# PT_2015_PB_MAIN_Rev2.net
KiCad netlist of a schematic drawn in EAGLE
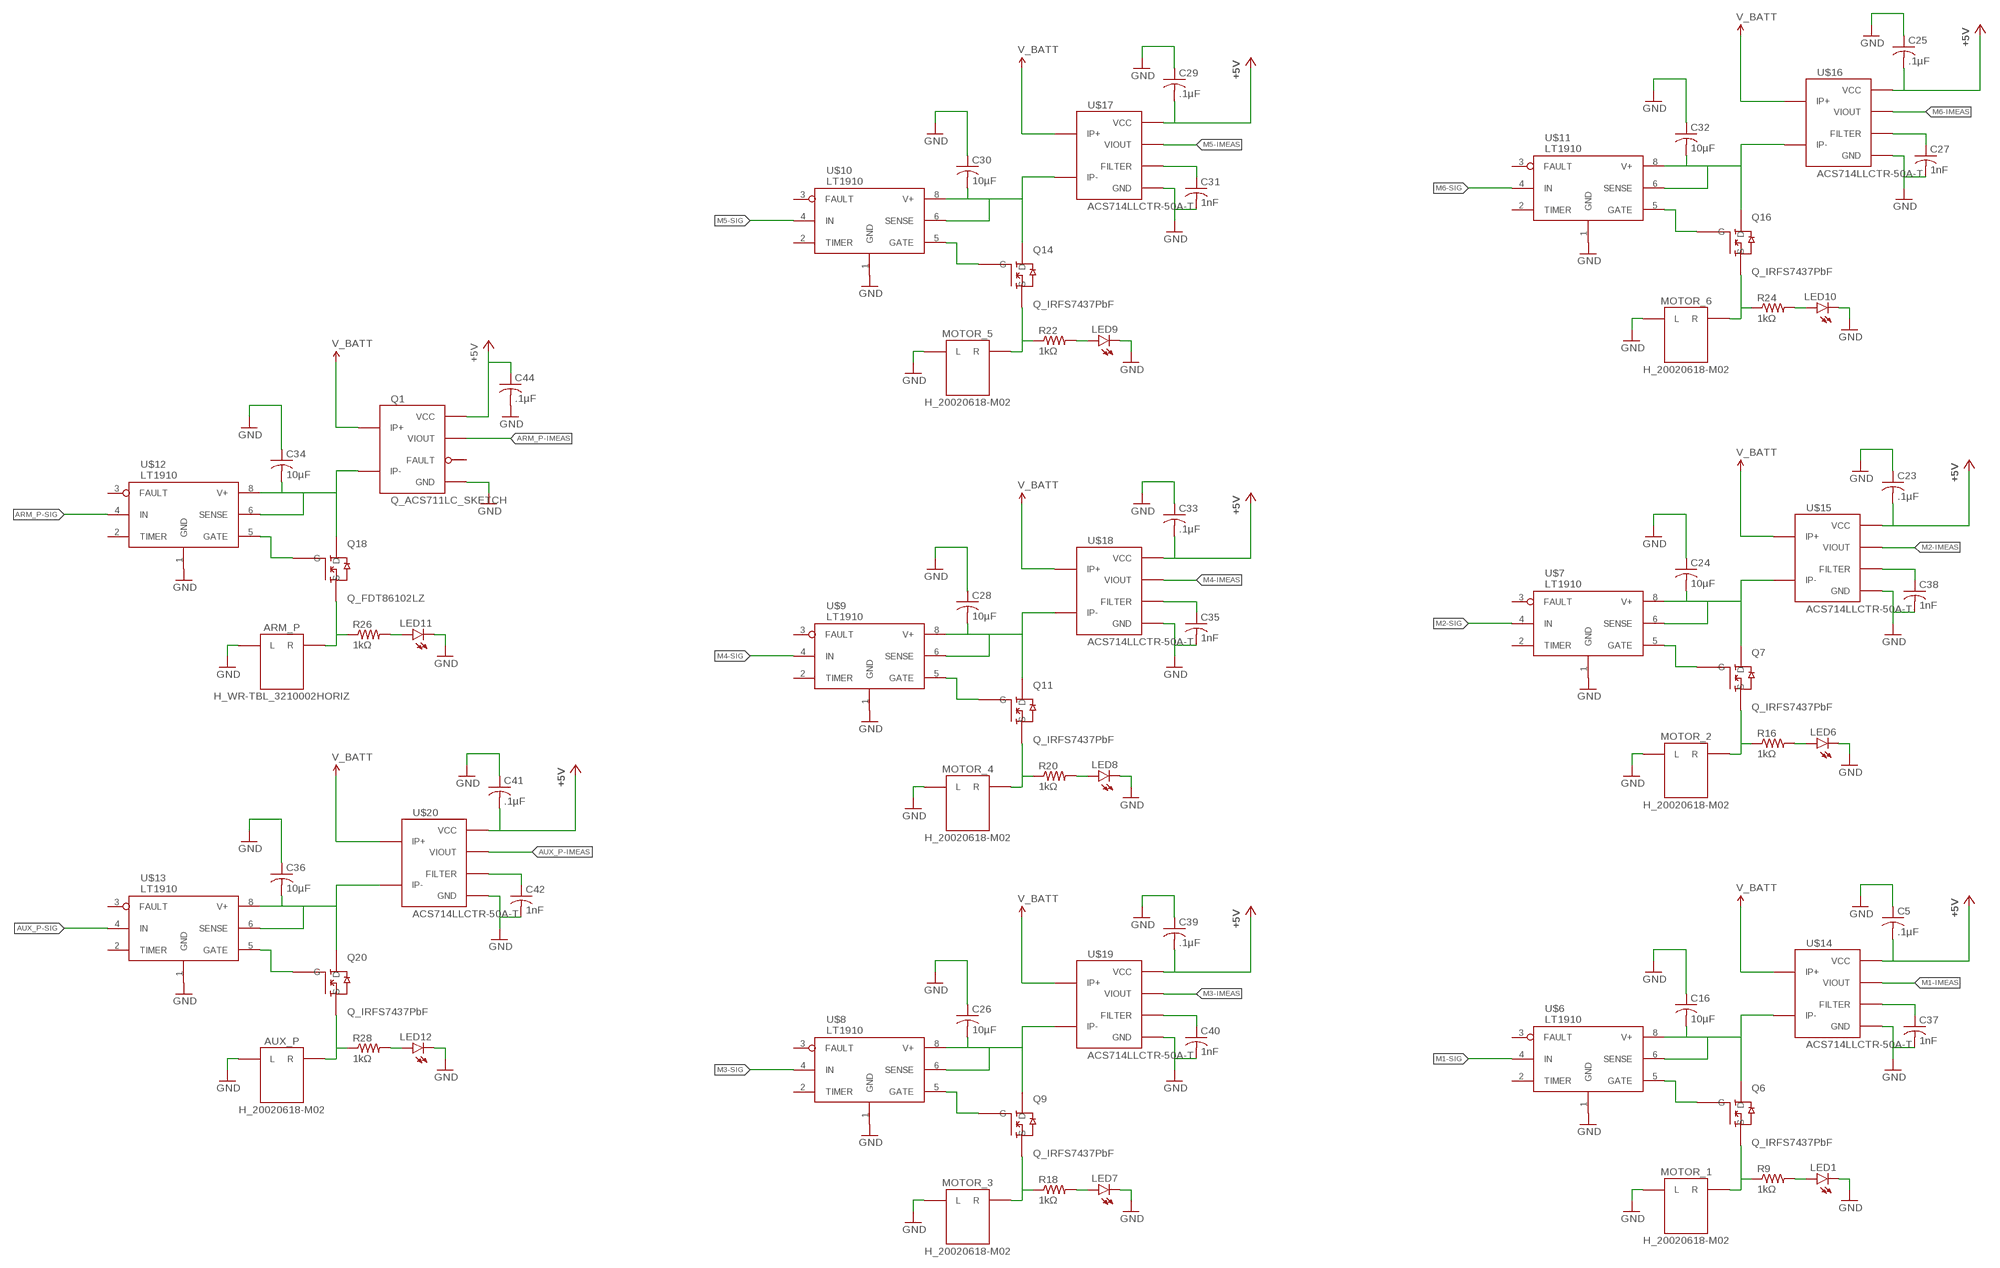
[diagram p0: schematic, sheet 1, part 1 of 3]
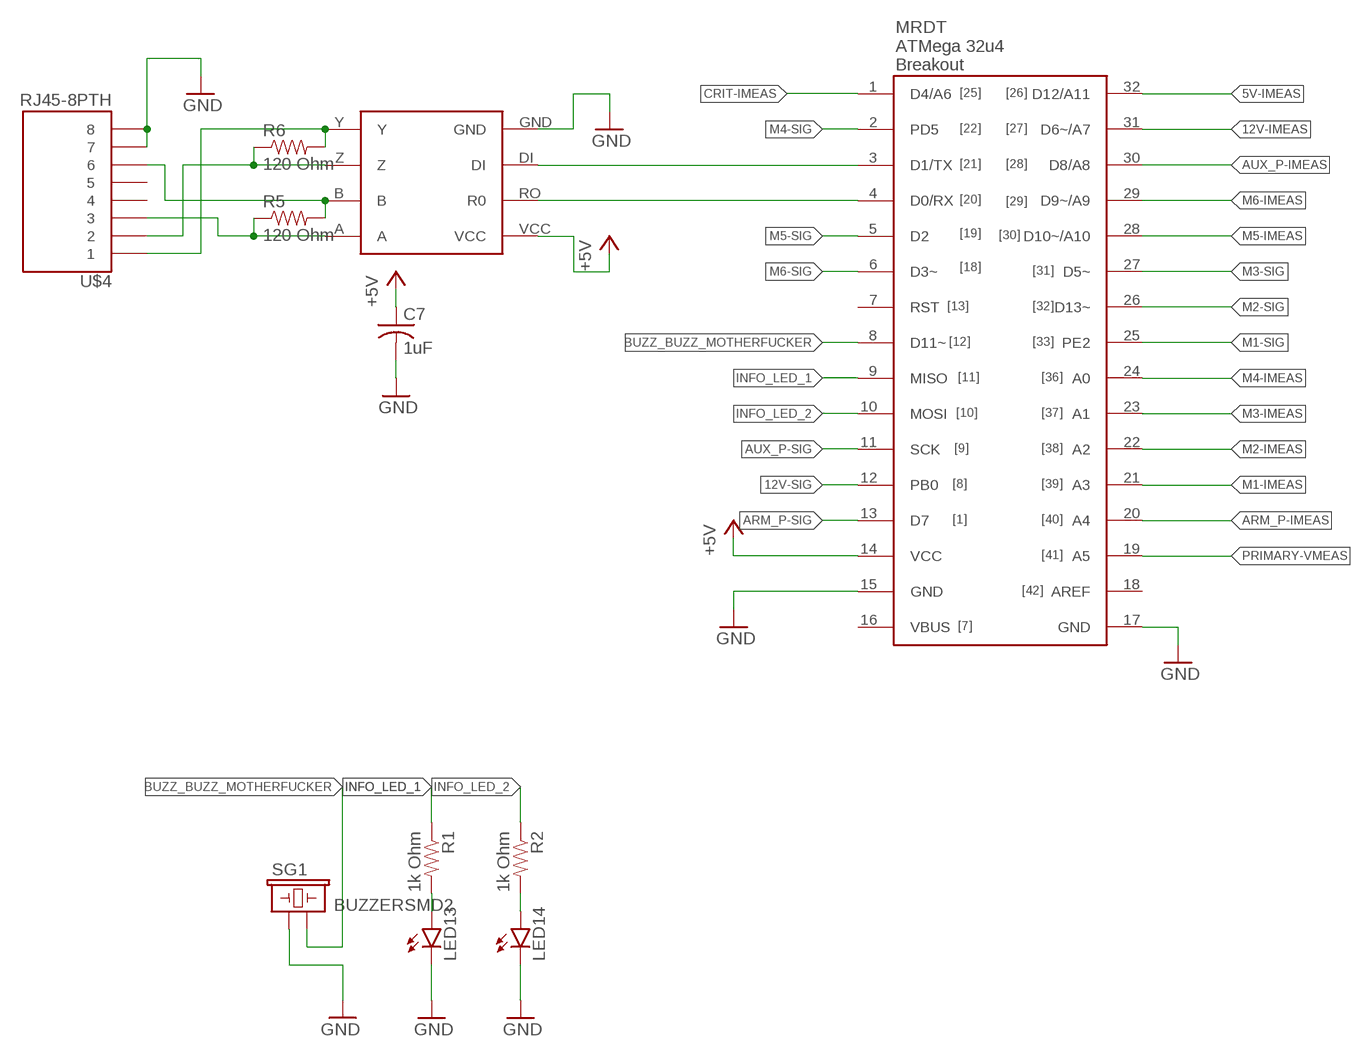
[diagram p1: schematic, sheet 1, part 2 of 3]
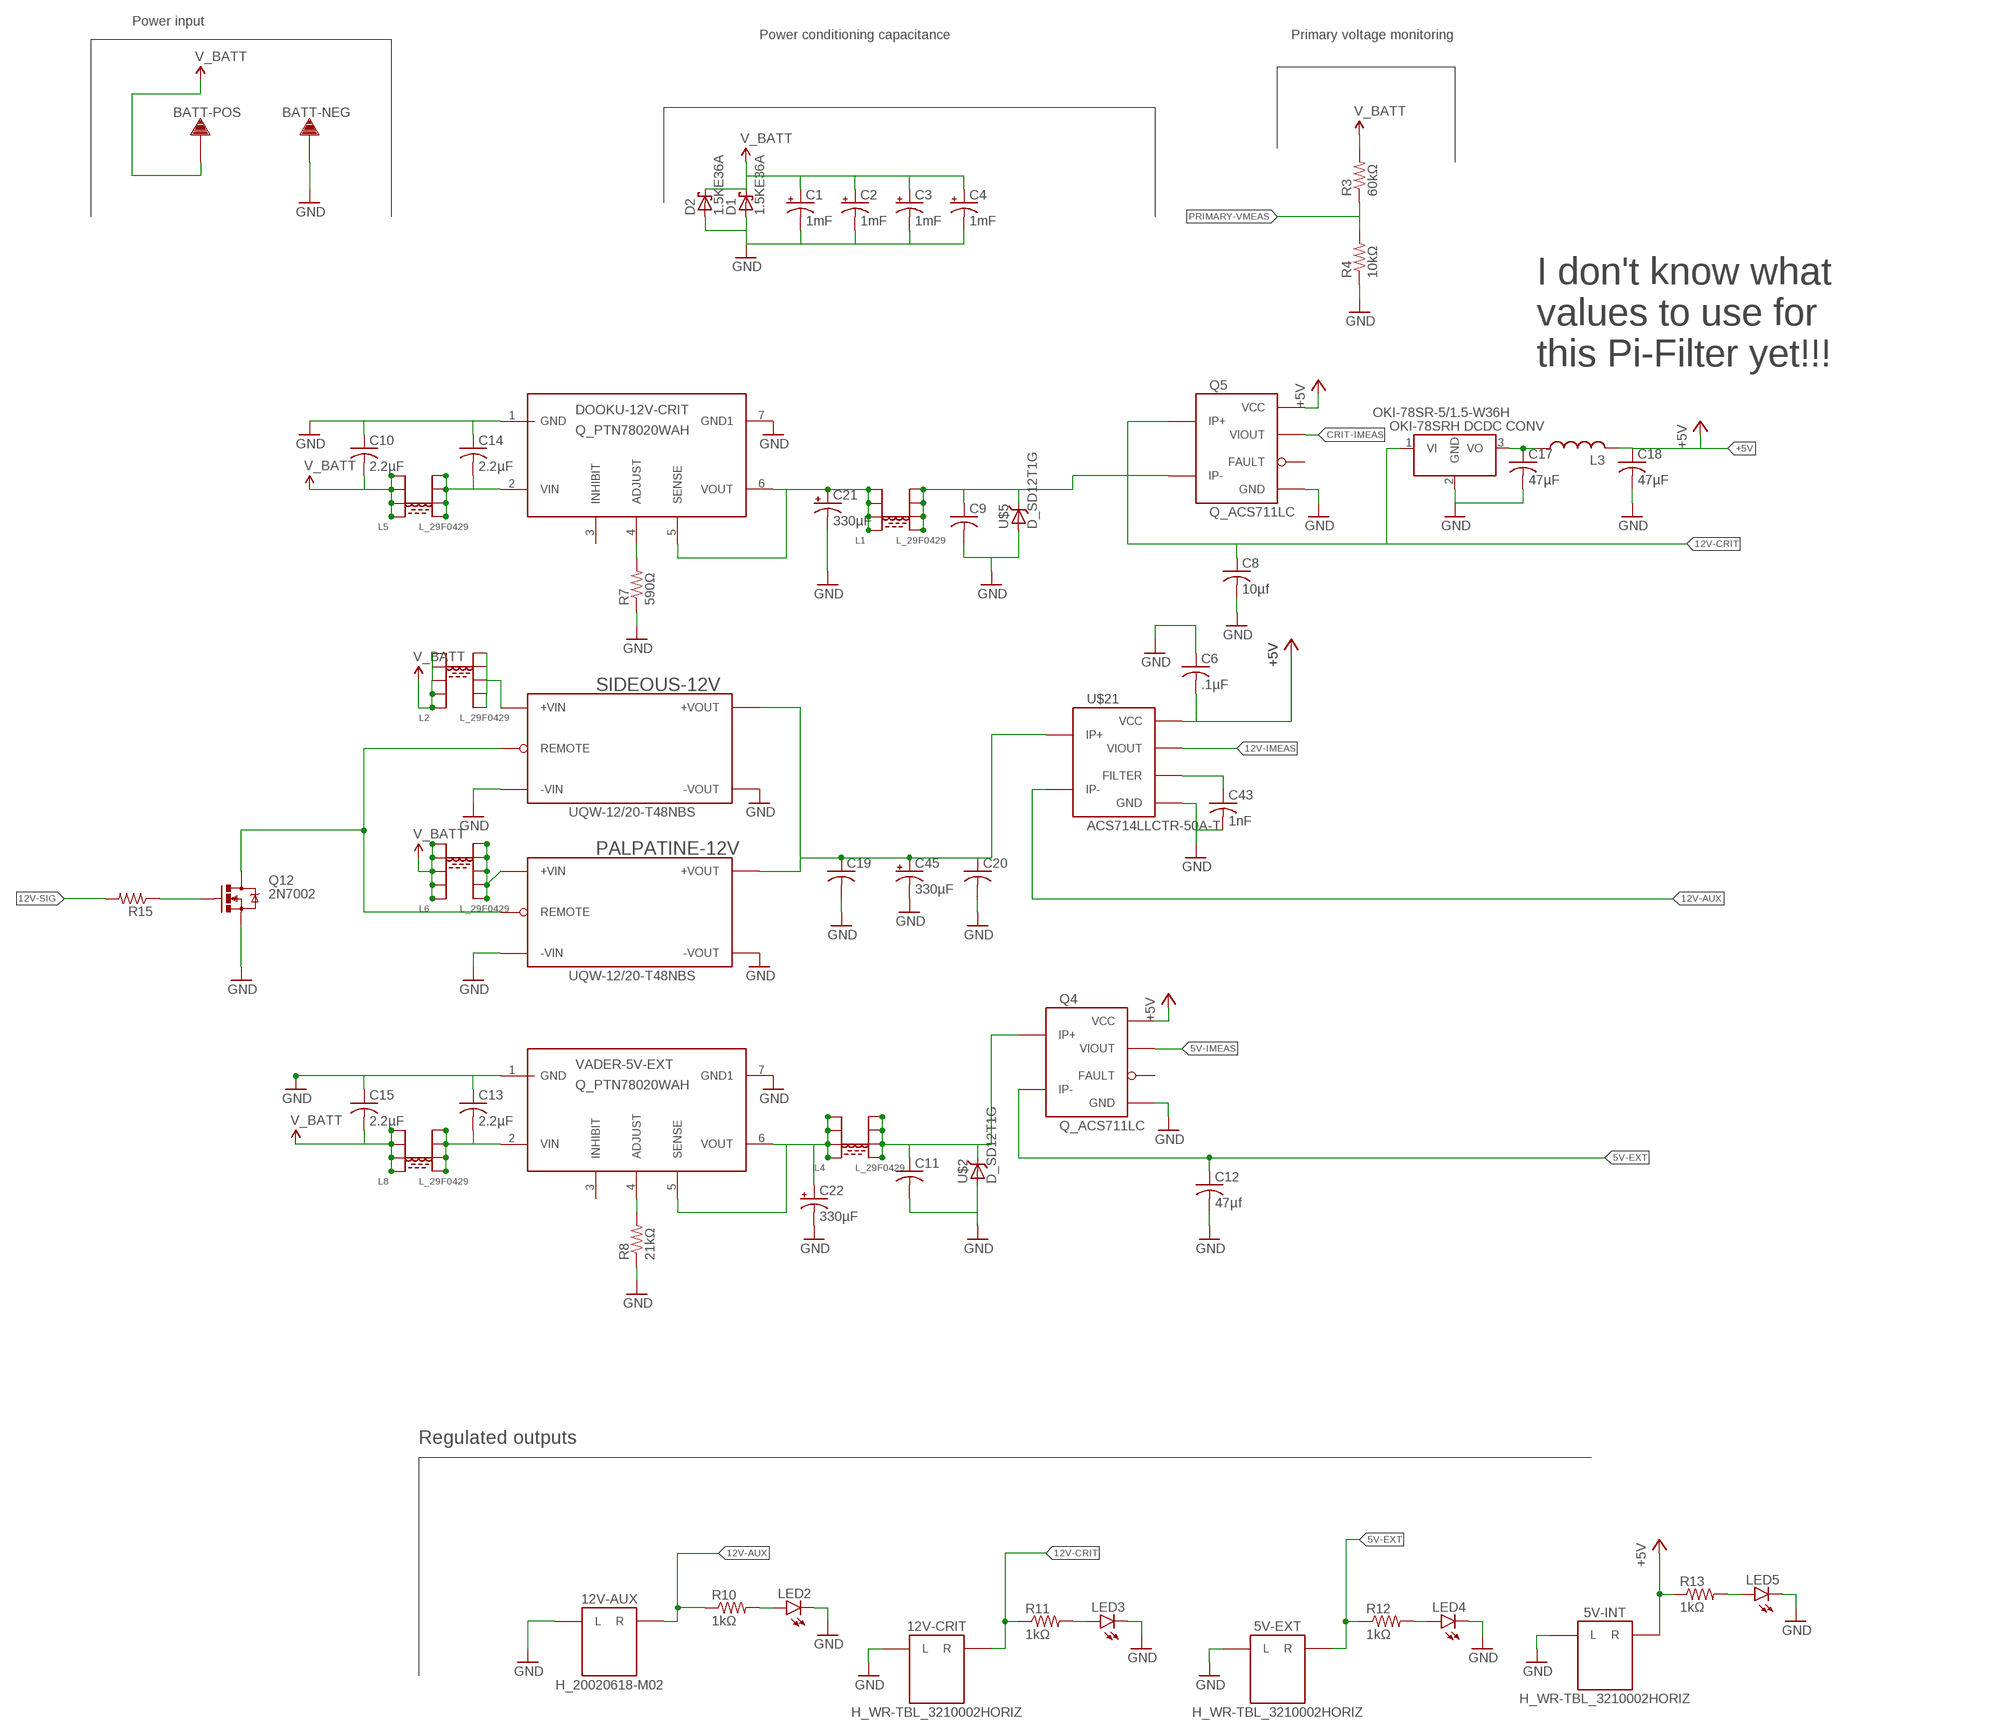
[diagram p2: schematic, sheet 1, part 3 of 3]

(export (version "E")
  (design (tool "Eeschema 10.0.6"))
  (components
    (comp (ref "5V-EXT")
      (value "H_WR-TBL_3210002HORIZ")
      (footprint "eagle-import:691322110002")
      (libsource (lib "eagle-import") (part "H_WR-TBL_3210002HORIZ"))
    )
    (comp (ref "5V-INT")
      (value "H_WR-TBL_3210002HORIZ")
      (footprint "eagle-import:691322110002")
      (libsource (lib "eagle-import") (part "H_WR-TBL_3210002HORIZ"))
    )
    (comp (ref "12V-AUX")
      (value "H_20020618-M02")
      (footprint "eagle-import:20020618-M02")
      (libsource (lib "eagle-import") (part "H_20020618-M02"))
    )
    (comp (ref "12V-CRIT")
      (value "H_WR-TBL_3210002HORIZ")
      (footprint "eagle-import:691322110002")
      (libsource (lib "eagle-import") (part "H_WR-TBL_3210002HORIZ"))
    )
    (comp (ref "ARM_P")
      (value "H_WR-TBL_3210002HORIZ")
      (footprint "eagle-import:691322110002")
      (libsource (lib "eagle-import") (part "H_WR-TBL_3210002HORIZ"))
    )
    (comp (ref "AUX_P")
      (value "H_20020618-M02")
      (footprint "eagle-import:20020618-M02")
      (libsource (lib "eagle-import") (part "H_20020618-M02"))
    )
    (comp (ref "BATT-NEG")
      (value "TERMINAL_HOLE")
      (footprint "eagle-import:LARGE_TERMINAL_HOLE")
      (libsource (lib "eagle-import") (part "TERMINAL_HOLE"))
    )
    (comp (ref "BATT-POS")
      (value "TERMINAL_HOLE")
      (footprint "eagle-import:LARGE_TERMINAL_HOLE")
      (libsource (lib "eagle-import") (part "TERMINAL_HOLE"))
    )
    (comp (ref "C1")
      (value "1mF")
      (footprint "eagle-import:C_12.5MM")
      (libsource (lib "eagle-import") (part "C_POL12.5MM_NORMAL"))
    )
    (comp (ref "C2")
      (value "1mF")
      (footprint "eagle-import:C_12.5MM")
      (libsource (lib "eagle-import") (part "C_POL12.5MM_NORMAL"))
    )
    (comp (ref "C3")
      (value "1mF")
      (footprint "eagle-import:C_12.5MM")
      (libsource (lib "eagle-import") (part "C_POL12.5MM_NORMAL"))
    )
    (comp (ref "C4")
      (value "1mF")
      (footprint "eagle-import:C_12.5MM")
      (libsource (lib "eagle-import") (part "C_POL12.5MM_NORMAL"))
    )
    (comp (ref "C5")
      (value ".1µF")
      (footprint "eagle-import:C1206")
      (libsource (lib "eagle-import") (part "C-USC1206"))
    )
    (comp (ref "C6")
      (value ".1µF")
      (footprint "eagle-import:C1206")
      (libsource (lib "eagle-import") (part "C-USC1206"))
    )
    (comp (ref "C7")
      (value "1uF")
      (footprint "eagle-import:C1206")
      (libsource (lib "eagle-import") (part "C-USC1206"))
    )
    (comp (ref "C8")
      (value "10µf")
      (footprint "eagle-import:C1206")
      (libsource (lib "eagle-import") (part "C-USC1206"))
    )
    (comp (ref "C9")
      (value "C-USC1206")
      (footprint "eagle-import:C1206")
      (libsource (lib "eagle-import") (part "C-USC1206"))
    )
    (comp (ref "C10")
      (value "2.2µF")
      (footprint "eagle-import:C1206")
      (libsource (lib "eagle-import") (part "C-USC1206"))
    )
    (comp (ref "C11")
      (value "C-USC1206")
      (footprint "eagle-import:C1206")
      (libsource (lib "eagle-import") (part "C-USC1206"))
    )
    (comp (ref "C12")
      (value "47µf")
      (footprint "eagle-import:C1206")
      (libsource (lib "eagle-import") (part "C-USC1206"))
    )
    (comp (ref "C13")
      (value "2.2µF")
      (footprint "eagle-import:C1206")
      (libsource (lib "eagle-import") (part "C-USC1206"))
    )
    (comp (ref "C14")
      (value "2.2µF")
      (footprint "eagle-import:C1206")
      (libsource (lib "eagle-import") (part "C-USC1206"))
    )
    (comp (ref "C15")
      (value "2.2µF")
      (footprint "eagle-import:C1206")
      (libsource (lib "eagle-import") (part "C-USC1206"))
    )
    (comp (ref "C16")
      (value "10µF")
      (footprint "eagle-import:C1206")
      (libsource (lib "eagle-import") (part "C-USC1206"))
    )
    (comp (ref "C17")
      (value "47µF")
      (footprint "eagle-import:C1206")
      (libsource (lib "eagle-import") (part "C-USC1206"))
    )
    (comp (ref "C18")
      (value "47µF")
      (footprint "eagle-import:C1206")
      (libsource (lib "eagle-import") (part "C-USC1206"))
    )
    (comp (ref "C19")
      (value "C-USC1206")
      (footprint "eagle-import:C1206")
      (libsource (lib "eagle-import") (part "C-USC1206"))
    )
    (comp (ref "C20")
      (value "C-USC1206")
      (footprint "eagle-import:C1206")
      (libsource (lib "eagle-import") (part "C-USC1206"))
    )
    (comp (ref "C21")
      (value "330µF")
      (footprint "eagle-import:E5-8,5")
      (libsource (lib "eagle-import") (part "CPOL-USE5-8.5"))
    )
    (comp (ref "C22")
      (value "330µF")
      (footprint "eagle-import:E5-8,5")
      (libsource (lib "eagle-import") (part "CPOL-USE5-8.5"))
    )
    (comp (ref "C23")
      (value ".1µF")
      (footprint "eagle-import:C1206")
      (libsource (lib "eagle-import") (part "C-USC1206"))
    )
    (comp (ref "C24")
      (value "10µF")
      (footprint "eagle-import:C1206")
      (libsource (lib "eagle-import") (part "C-USC1206"))
    )
    (comp (ref "C25")
      (value ".1µF")
      (footprint "eagle-import:C1206")
      (libsource (lib "eagle-import") (part "C-USC1206"))
    )
    (comp (ref "C26")
      (value "10µF")
      (footprint "eagle-import:C1206")
      (libsource (lib "eagle-import") (part "C-USC1206"))
    )
    (comp (ref "C27")
      (value "1nF")
      (footprint "eagle-import:C0805")
      (libsource (lib "eagle-import") (part "C-USC0805"))
    )
    (comp (ref "C28")
      (value "10µF")
      (footprint "eagle-import:C1206")
      (libsource (lib "eagle-import") (part "C-USC1206"))
    )
    (comp (ref "C29")
      (value ".1µF")
      (footprint "eagle-import:C1206")
      (libsource (lib "eagle-import") (part "C-USC1206"))
    )
    (comp (ref "C30")
      (value "10µF")
      (footprint "eagle-import:C1206")
      (libsource (lib "eagle-import") (part "C-USC1206"))
    )
    (comp (ref "C31")
      (value "1nF")
      (footprint "eagle-import:C0805")
      (libsource (lib "eagle-import") (part "C-USC0805"))
    )
    (comp (ref "C32")
      (value "10µF")
      (footprint "eagle-import:C1206")
      (libsource (lib "eagle-import") (part "C-USC1206"))
    )
    (comp (ref "C33")
      (value ".1µF")
      (footprint "eagle-import:C1206")
      (libsource (lib "eagle-import") (part "C-USC1206"))
    )
    (comp (ref "C34")
      (value "10µF")
      (footprint "eagle-import:C1206")
      (libsource (lib "eagle-import") (part "C-USC1206"))
    )
    (comp (ref "C35")
      (value "1nF")
      (footprint "eagle-import:C0805")
      (libsource (lib "eagle-import") (part "C-USC0805"))
    )
    (comp (ref "C36")
      (value "10µF")
      (footprint "eagle-import:C1206")
      (libsource (lib "eagle-import") (part "C-USC1206"))
    )
    (comp (ref "C37")
      (value "1nF")
      (footprint "eagle-import:C0805")
      (libsource (lib "eagle-import") (part "C-USC0805"))
    )
    (comp (ref "C38")
      (value "1nF")
      (footprint "eagle-import:C0805")
      (libsource (lib "eagle-import") (part "C-USC0805"))
    )
    (comp (ref "C39")
      (value ".1µF")
      (footprint "eagle-import:C1206")
      (libsource (lib "eagle-import") (part "C-USC1206"))
    )
    (comp (ref "C40")
      (value "1nF")
      (footprint "eagle-import:C0805")
      (libsource (lib "eagle-import") (part "C-USC0805"))
    )
    (comp (ref "C41")
      (value ".1µF")
      (footprint "eagle-import:C1206")
      (libsource (lib "eagle-import") (part "C-USC1206"))
    )
    (comp (ref "C42")
      (value "1nF")
      (footprint "eagle-import:C0805")
      (libsource (lib "eagle-import") (part "C-USC0805"))
    )
    (comp (ref "C43")
      (value "1nF")
      (footprint "eagle-import:C0805")
      (libsource (lib "eagle-import") (part "C-USC0805"))
    )
    (comp (ref "C44")
      (value ".1µF")
      (footprint "eagle-import:C1206")
      (libsource (lib "eagle-import") (part "C-USC1206"))
    )
    (comp (ref "C45")
      (value "330µF")
      (footprint "eagle-import:E5-8,5")
      (libsource (lib "eagle-import") (part "CPOL-USE5-8.5"))
    )
    (comp (ref "D1")
      (value "1.5KE36A")
      (footprint "eagle-import:CB429-17")
      (libsource (lib "eagle-import") (part "15KEXX"))
    )
    (comp (ref "D2")
      (value "1.5KE36A")
      (footprint "eagle-import:CB429-17")
      (libsource (lib "eagle-import") (part "15KEXX"))
    )
    (comp (ref "DOOKU-12V-CRIT")
      (value "Q_PTN78020WAH")
      (footprint "eagle-import:R_PDSS-T7")
      (libsource (lib "eagle-import") (part "Q_PTN78020"))
    )
    (comp (ref "L1")
      (value "L_29F0429")
      (footprint "eagle-import:L_29F0429")
      (libsource (lib "eagle-import") (part "L_29F0429"))
    )
    (comp (ref "L2")
      (value "L_29F0429")
      (footprint "eagle-import:L_29F0528")
      (libsource (lib "eagle-import") (part "MRDT-2015-PowerBoard_L_29F0429"))
    )
    (comp (ref "L3")
      (value "L-USL3216C")
      (footprint "eagle-import:L3216C")
      (libsource (lib "eagle-import") (part "L-USL3216C"))
    )
    (comp (ref "L4")
      (value "L_29F0429")
      (footprint "eagle-import:L_29F0429")
      (libsource (lib "eagle-import") (part "L_29F0429"))
    )
    (comp (ref "L5")
      (value "L_29F0429")
      (footprint "eagle-import:L_29F0429")
      (libsource (lib "eagle-import") (part "L_29F0429"))
    )
    (comp (ref "L6")
      (value "L_29F0429")
      (footprint "eagle-import:L_29F0528")
      (libsource (lib "eagle-import") (part "MRDT-2015-PowerBoard_L_29F0429"))
    )
    (comp (ref "L8")
      (value "L_29F0429")
      (footprint "eagle-import:L_29F0429")
      (libsource (lib "eagle-import") (part "L_29F0429"))
    )
    (comp (ref "LED1")
      (value "LED1206")
      (footprint "eagle-import:LED-1206")
      (libsource (lib "eagle-import") (part "LED1206"))
    )
    (comp (ref "LED2")
      (value "LED1206")
      (footprint "eagle-import:LED-1206")
      (libsource (lib "eagle-import") (part "LED1206"))
    )
    (comp (ref "LED3")
      (value "LED1206")
      (footprint "eagle-import:LED-1206")
      (libsource (lib "eagle-import") (part "LED1206"))
    )
    (comp (ref "LED4")
      (value "LED1206")
      (footprint "eagle-import:LED-1206")
      (libsource (lib "eagle-import") (part "LED1206"))
    )
    (comp (ref "LED5")
      (value "LED1206")
      (footprint "eagle-import:LED-1206")
      (libsource (lib "eagle-import") (part "LED1206"))
    )
    (comp (ref "LED6")
      (value "LED1206")
      (footprint "eagle-import:LED-1206")
      (libsource (lib "eagle-import") (part "LED1206"))
    )
    (comp (ref "LED7")
      (value "LED1206")
      (footprint "eagle-import:LED-1206")
      (libsource (lib "eagle-import") (part "LED1206"))
    )
    (comp (ref "LED8")
      (value "LED1206")
      (footprint "eagle-import:LED-1206")
      (libsource (lib "eagle-import") (part "LED1206"))
    )
    (comp (ref "LED9")
      (value "LED1206")
      (footprint "eagle-import:LED-1206")
      (libsource (lib "eagle-import") (part "LED1206"))
    )
    (comp (ref "LED10")
      (value "LED1206")
      (footprint "eagle-import:LED-1206")
      (libsource (lib "eagle-import") (part "LED1206"))
    )
    (comp (ref "LED11")
      (value "LED1206")
      (footprint "eagle-import:LED-1206")
      (libsource (lib "eagle-import") (part "LED1206"))
    )
    (comp (ref "LED12")
      (value "LED1206")
      (footprint "eagle-import:LED-1206")
      (libsource (lib "eagle-import") (part "LED1206"))
    )
    (comp (ref "LED13")
      (value "LED-FKIT-1206")
      (footprint "eagle-import:FKIT-LED-1206")
      (libsource (lib "eagle-import") (part "LED-FKIT-1206"))
    )
    (comp (ref "LED14")
      (value "LED-FKIT-1206")
      (footprint "eagle-import:FKIT-LED-1206")
      (libsource (lib "eagle-import") (part "LED-FKIT-1206"))
    )
    (comp (ref "MOTOR_1")
      (value "H_20020618-M02")
      (footprint "eagle-import:20020618-M02")
      (libsource (lib "eagle-import") (part "H_20020618-M02"))
    )
    (comp (ref "MOTOR_2")
      (value "H_20020618-M02")
      (footprint "eagle-import:20020618-M02")
      (libsource (lib "eagle-import") (part "H_20020618-M02"))
    )
    (comp (ref "MOTOR_3")
      (value "H_20020618-M02")
      (footprint "eagle-import:20020618-M02")
      (libsource (lib "eagle-import") (part "H_20020618-M02"))
    )
    (comp (ref "MOTOR_4")
      (value "H_20020618-M02")
      (footprint "eagle-import:20020618-M02")
      (libsource (lib "eagle-import") (part "H_20020618-M02"))
    )
    (comp (ref "MOTOR_5")
      (value "H_20020618-M02")
      (footprint "eagle-import:20020618-M02")
      (libsource (lib "eagle-import") (part "H_20020618-M02"))
    )
    (comp (ref "MOTOR_6")
      (value "H_20020618-M02")
      (footprint "eagle-import:20020618-M02")
      (libsource (lib "eagle-import") (part "H_20020618-M02"))
    )
    (comp (ref "OKI-78SR-5/1.5-W36H")
      (value "Q_OKI-78SR")
      (footprint "eagle-import:OKI-78SRH")
      (libsource (lib "eagle-import") (part "Q_OKI-78SR"))
    )
    (comp (ref "PALPATINE-12V")
      (value "UQW-12/20-T48NBS")
      (footprint "eagle-import:U-T48-QB-NO_TRIM")
      (libsource (lib "eagle-import") (part "UQW-12/20-T48NBS"))
    )
    (comp (ref "Q1")
      (value "Q_ACS711LC_SKETCH")
      (footprint "eagle-import:SOIC8_ACS711_SKETCH")
      (libsource (lib "eagle-import") (part "Q_ACS711LC_SKETCH"))
    )
    (comp (ref "Q4")
      (value "Q_ACS711LC")
      (footprint "eagle-import:SOIC8_ACS711")
      (libsource (lib "eagle-import") (part "Q_ACS711LC"))
    )
    (comp (ref "Q5")
      (value "Q_ACS711LC")
      (footprint "eagle-import:SOIC8_ACS711")
      (libsource (lib "eagle-import") (part "Q_ACS711LC"))
    )
    (comp (ref "Q6")
      (value "Q_IRFS7437PbF")
      (footprint "eagle-import:D2PACK")
      (libsource (lib "eagle-import") (part "Q_IRF7437SMD"))
    )
    (comp (ref "Q7")
      (value "Q_IRFS7437PbF")
      (footprint "eagle-import:D2PACK")
      (libsource (lib "eagle-import") (part "Q_IRF7437SMD"))
    )
    (comp (ref "Q9")
      (value "Q_IRFS7437PbF")
      (footprint "eagle-import:D2PACK")
      (libsource (lib "eagle-import") (part "Q_IRF7437SMD"))
    )
    (comp (ref "Q11")
      (value "Q_IRFS7437PbF")
      (footprint "eagle-import:D2PACK")
      (libsource (lib "eagle-import") (part "Q_IRF7437SMD"))
    )
    (comp (ref "Q12")
      (value "2N7002")
      (footprint "eagle-import:SOT323")
      (libsource (lib "eagle-import") (part "MOSFET-NCHANNEL2N7002PW"))
    )
    (comp (ref "Q14")
      (value "Q_IRFS7437PbF")
      (footprint "eagle-import:D2PACK")
      (libsource (lib "eagle-import") (part "Q_IRF7437SMD"))
    )
    (comp (ref "Q16")
      (value "Q_IRFS7437PbF")
      (footprint "eagle-import:D2PACK")
      (libsource (lib "eagle-import") (part "Q_IRF7437SMD"))
    )
    (comp (ref "Q18")
      (value "Q_FDT86102LZ")
      (footprint "eagle-import:SOT-223")
      (libsource (lib "eagle-import") (part "Q_FDT86102LZ"))
    )
    (comp (ref "Q20")
      (value "Q_IRFS7437PbF")
      (footprint "eagle-import:D2PACK")
      (libsource (lib "eagle-import") (part "Q_IRF7437SMD"))
    )
    (comp (ref "R1")
      (value "1k Ohm")
      (footprint "eagle-import:1206")
      (libsource (lib "eagle-import") (part "RESISTOR1206"))
    )
    (comp (ref "R2")
      (value "1k Ohm")
      (footprint "eagle-import:1206")
      (libsource (lib "eagle-import") (part "RESISTOR1206"))
    )
    (comp (ref "R3")
      (value "60kΩ")
      (footprint "eagle-import:R1206")
      (libsource (lib "eagle-import") (part "R-US_R1206"))
    )
    (comp (ref "R4")
      (value "10kΩ")
      (footprint "eagle-import:R1206")
      (libsource (lib "eagle-import") (part "R-US_R1206"))
    )
    (comp (ref "R5")
      (value "120 Ohm")
      (footprint "eagle-import:1206")
      (libsource (lib "eagle-import") (part "RESISTOR1206"))
    )
    (comp (ref "R6")
      (value "120 Ohm")
      (footprint "eagle-import:1206")
      (libsource (lib "eagle-import") (part "RESISTOR1206"))
    )
    (comp (ref "R7")
      (value "590Ω")
      (footprint "eagle-import:R1206")
      (libsource (lib "eagle-import") (part "R-US_R1206"))
    )
    (comp (ref "R8")
      (value "21kΩ")
      (footprint "eagle-import:R1206")
      (libsource (lib "eagle-import") (part "R-US_R1206"))
    )
    (comp (ref "R9")
      (value "1kΩ")
      (footprint "eagle-import:1206")
      (libsource (lib "eagle-import") (part "RESISTOR1206"))
    )
    (comp (ref "R10")
      (value "1kΩ")
      (footprint "eagle-import:1206")
      (libsource (lib "eagle-import") (part "RESISTOR1206"))
    )
    (comp (ref "R11")
      (value "1kΩ")
      (footprint "eagle-import:1206")
      (libsource (lib "eagle-import") (part "RESISTOR1206"))
    )
    (comp (ref "R12")
      (value "1kΩ")
      (footprint "eagle-import:1206")
      (libsource (lib "eagle-import") (part "RESISTOR1206"))
    )
    (comp (ref "R13")
      (value "1kΩ")
      (footprint "eagle-import:1206")
      (libsource (lib "eagle-import") (part "RESISTOR1206"))
    )
    (comp (ref "R15")
      (value "R-US_R1206")
      (footprint "eagle-import:R1206")
      (libsource (lib "eagle-import") (part "R-US_R1206"))
    )
    (comp (ref "R16")
      (value "1kΩ")
      (footprint "eagle-import:1206")
      (libsource (lib "eagle-import") (part "RESISTOR1206"))
    )
    (comp (ref "R18")
      (value "1kΩ")
      (footprint "eagle-import:1206")
      (libsource (lib "eagle-import") (part "RESISTOR1206"))
    )
    (comp (ref "R20")
      (value "1kΩ")
      (footprint "eagle-import:1206")
      (libsource (lib "eagle-import") (part "RESISTOR1206"))
    )
    (comp (ref "R22")
      (value "1kΩ")
      (footprint "eagle-import:1206")
      (libsource (lib "eagle-import") (part "RESISTOR1206"))
    )
    (comp (ref "R24")
      (value "1kΩ")
      (footprint "eagle-import:1206")
      (libsource (lib "eagle-import") (part "RESISTOR1206"))
    )
    (comp (ref "R26")
      (value "1kΩ")
      (footprint "eagle-import:1206")
      (libsource (lib "eagle-import") (part "RESISTOR1206"))
    )
    (comp (ref "R28")
      (value "1kΩ")
      (footprint "eagle-import:1206")
      (libsource (lib "eagle-import") (part "RESISTOR1206"))
    )
    (comp (ref "SG1")
      (value "BUZZERSMD2")
      (footprint "eagle-import:BUZZER-CCV")
      (libsource (lib "eagle-import") (part "BUZZERSMD2"))
    )
    (comp (ref "SIDEOUS-12V")
      (value "UQW-12/20-T48NBS")
      (footprint "eagle-import:U-T48-QB-NO_TRIM")
      (libsource (lib "eagle-import") (part "UQW-12/20-T48NBS"))
    )
    (comp (ref "U$1")
      (value "32U4_BREAKOUT")
      (footprint "eagle-import:32U4_MCU_DIP")
      (libsource (lib "eagle-import") (part "32U4_BREAKOUT"))
    )
    (comp (ref "U$2")
      (value "D_SD12T1G")
      (footprint "eagle-import:SOD-323")
      (libsource (lib "eagle-import") (part "D_SD12T1G"))
    )
    (comp (ref "U$3")
      (value "MAX3077")
      (footprint "eagle-import:MAX3070E")
      (libsource (lib "eagle-import") (part "MAX3077"))
    )
    (comp (ref "U$4")
      (value "RJ45-8PTH")
      (footprint "eagle-import:RJ45-8")
      (libsource (lib "eagle-import") (part "RJ45-8PTH"))
    )
    (comp (ref "U$5")
      (value "D_SD12T1G")
      (footprint "eagle-import:SOD-323")
      (libsource (lib "eagle-import") (part "D_SD12T1G"))
    )
    (comp (ref "U$6")
      (value "LT1910")
      (footprint "eagle-import:SO8")
      (libsource (lib "eagle-import") (part "LT1910"))
    )
    (comp (ref "U$7")
      (value "LT1910")
      (footprint "eagle-import:SO8")
      (libsource (lib "eagle-import") (part "LT1910"))
    )
    (comp (ref "U$8")
      (value "LT1910")
      (footprint "eagle-import:SO8")
      (libsource (lib "eagle-import") (part "LT1910"))
    )
    (comp (ref "U$9")
      (value "LT1910")
      (footprint "eagle-import:SO8")
      (libsource (lib "eagle-import") (part "LT1910"))
    )
    (comp (ref "U$10")
      (value "LT1910")
      (footprint "eagle-import:SO8")
      (libsource (lib "eagle-import") (part "LT1910"))
    )
    (comp (ref "U$11")
      (value "LT1910")
      (footprint "eagle-import:SO8")
      (libsource (lib "eagle-import") (part "LT1910"))
    )
    (comp (ref "U$12")
      (value "LT1910")
      (footprint "eagle-import:SO8")
      (libsource (lib "eagle-import") (part "LT1910"))
    )
    (comp (ref "U$13")
      (value "LT1910")
      (footprint "eagle-import:SO8")
      (libsource (lib "eagle-import") (part "LT1910"))
    )
    (comp (ref "U$14")
      (value "ACS714LLCTR-50A-T")
      (footprint "eagle-import:SOIC8_ACS711_SKETCH")
      (libsource (lib "eagle-import") (part "Q_ACS714_SKETCH"))
    )
    (comp (ref "U$15")
      (value "ACS714LLCTR-50A-T")
      (footprint "eagle-import:SOIC8_ACS711_SKETCH")
      (libsource (lib "eagle-import") (part "Q_ACS714_SKETCH"))
    )
    (comp (ref "U$16")
      (value "ACS714LLCTR-50A-T")
      (footprint "eagle-import:SOIC8_ACS711_SKETCH")
      (libsource (lib "eagle-import") (part "Q_ACS714_SKETCH"))
    )
    (comp (ref "U$17")
      (value "ACS714LLCTR-50A-T")
      (footprint "eagle-import:SOIC8_ACS711_SKETCH")
      (libsource (lib "eagle-import") (part "Q_ACS714_SKETCH"))
    )
    (comp (ref "U$18")
      (value "ACS714LLCTR-50A-T")
      (footprint "eagle-import:SOIC8_ACS711_SKETCH")
      (libsource (lib "eagle-import") (part "Q_ACS714_SKETCH"))
    )
    (comp (ref "U$19")
      (value "ACS714LLCTR-50A-T")
      (footprint "eagle-import:SOIC8_ACS711_SKETCH")
      (libsource (lib "eagle-import") (part "Q_ACS714_SKETCH"))
    )
    (comp (ref "U$20")
      (value "ACS714LLCTR-50A-T")
      (footprint "eagle-import:SOIC8_ACS711_SKETCH")
      (libsource (lib "eagle-import") (part "Q_ACS714_SKETCH"))
    )
    (comp (ref "U$21")
      (value "ACS714LLCTR-50A-T")
      (footprint "eagle-import:SOIC8_ACS711")
      (libsource (lib "eagle-import") (part "Q_ACS714"))
    )
    (comp (ref "VADER-5V-EXT")
      (value "Q_PTN78020WAH")
      (footprint "eagle-import:R_PDSS-T7")
      (libsource (lib "eagle-import") (part "Q_PTN78020"))
    )
  )
  (nets
    (net (code "1") (name "+5V") (class "Default")
      (node (ref "5V-INT") (pin "R") (pinfunction "R_R") (pintype "bidirectional"))
      (node (ref "C18") (pin "1") (pinfunction "1_1") (pintype "passive"))
      (node (ref "C23") (pin "2") (pinfunction "2_2") (pintype "passive"))
      (node (ref "C25") (pin "2") (pinfunction "2_2") (pintype "passive"))
      (node (ref "C29") (pin "2") (pinfunction "2_2") (pintype "passive"))
      (node (ref "C33") (pin "2") (pinfunction "2_2") (pintype "passive"))
      (node (ref "C39") (pin "2") (pinfunction "2_2") (pintype "passive"))
      (node (ref "C41") (pin "2") (pinfunction "2_2") (pintype "passive"))
      (node (ref "C44") (pin "1") (pinfunction "1_1") (pintype "passive"))
      (node (ref "C5") (pin "2") (pinfunction "2_2") (pintype "passive"))
      (node (ref "C6") (pin "2") (pinfunction "2_2") (pintype "passive"))
      (node (ref "C7") (pin "1") (pinfunction "1_1") (pintype "passive"))
      (node (ref "L3") (pin "2") (pinfunction "2_2") (pintype "passive"))
      (node (ref "Q1") (pin "8") (pinfunction "VCC_8") (pintype "bidirectional"))
      (node (ref "Q4") (pin "8") (pinfunction "VCC_8") (pintype "bidirectional"))
      (node (ref "Q5") (pin "8") (pinfunction "VCC_8") (pintype "bidirectional"))
      (node (ref "R13") (pin "1") (pinfunction "1_1") (pintype "passive"))
      (node (ref "U$1") (pin "14") (pinfunction "VCC_14") (pintype "bidirectional"))
      (node (ref "U$14") (pin "8") (pinfunction "VCC_8") (pintype "bidirectional"))
      (node (ref "U$15") (pin "8") (pinfunction "VCC_8") (pintype "bidirectional"))
      (node (ref "U$16") (pin "8") (pinfunction "VCC_8") (pintype "bidirectional"))
      (node (ref "U$17") (pin "8") (pinfunction "VCC_8") (pintype "bidirectional"))
      (node (ref "U$18") (pin "8") (pinfunction "VCC_8") (pintype "bidirectional"))
      (node (ref "U$19") (pin "8") (pinfunction "VCC_8") (pintype "bidirectional"))
      (node (ref "U$20") (pin "8") (pinfunction "VCC_8") (pintype "bidirectional"))
      (node (ref "U$21") (pin "8") (pinfunction "VCC_8") (pintype "bidirectional"))
      (node (ref "U$3") (pin "VCC") (pinfunction "VCC_VCC") (pintype "bidirectional"))
    )
    (net (code "2") (name "5V-EXT") (class "Default")
      (node (ref "5V-EXT") (pin "R") (pinfunction "R_R") (pintype "bidirectional"))
      (node (ref "C12") (pin "1") (pinfunction "1_1") (pintype "passive"))
      (node (ref "Q4") (pin "4") (pinfunction "IP-_4") (pintype "bidirectional"))
      (node (ref "R12") (pin "1") (pinfunction "1_1") (pintype "passive"))
    )
    (net (code "3") (name "5V-IMEAS") (class "Default")
      (node (ref "Q4") (pin "7") (pinfunction "VIOUT_7") (pintype "bidirectional"))
      (node (ref "U$1") (pin "32") (pinfunction "D12/A11_32") (pintype "bidirectional"))
    )
    (net (code "4") (name "12V-AUX") (class "Default")
      (node (ref "12V-AUX") (pin "R1") (pinfunction "R_R1") (pintype "bidirectional"))
      (node (ref "12V-AUX") (pin "R2") (pinfunction "R_R2") (pintype "bidirectional"))
      (node (ref "R10") (pin "1") (pinfunction "1_1") (pintype "passive"))
      (node (ref "U$21") (pin "4") (pinfunction "IP-_4") (pintype "bidirectional"))
    )
    (net (code "5") (name "12V-CRIT") (class "Default")
      (node (ref "12V-CRIT") (pin "R") (pinfunction "R_R") (pintype "bidirectional"))
      (node (ref "C8") (pin "1") (pinfunction "1_1") (pintype "passive"))
      (node (ref "OKI-78SR-5/1.5-W36H") (pin "1") (pinfunction "VI_1") (pintype "bidirectional"))
      (node (ref "Q5") (pin "1") (pinfunction "IP+_1") (pintype "bidirectional"))
      (node (ref "R11") (pin "1") (pinfunction "1_1") (pintype "passive"))
    )
    (net (code "6") (name "12V-IMEAS") (class "Default")
      (node (ref "U$1") (pin "31") (pinfunction "D6~{/A7}_31") (pintype "bidirectional"))
      (node (ref "U$21") (pin "7") (pinfunction "VIOUT_7") (pintype "bidirectional"))
    )
    (net (code "7") (name "12V-SIG") (class "Default")
      (node (ref "R15") (pin "2") (pinfunction "2_2") (pintype "passive"))
      (node (ref "U$1") (pin "12") (pinfunction "PB0_12") (pintype "bidirectional"))
    )
    (net (code "8") (name "ARM_P-IMEAS") (class "Default")
      (node (ref "Q1") (pin "7") (pinfunction "VIOUT_7") (pintype "bidirectional"))
      (node (ref "U$1") (pin "20") (pinfunction "A4_20") (pintype "bidirectional"))
    )
    (net (code "9") (name "ARM_P-SIG") (class "Default")
      (node (ref "U$1") (pin "13") (pinfunction "D7_13") (pintype "bidirectional"))
      (node (ref "U$12") (pin "4") (pinfunction "IN_4") (pintype "bidirectional"))
    )
    (net (code "10") (name "AUX_P-IMEAS") (class "Default")
      (node (ref "U$1") (pin "30") (pinfunction "D8/A8_30") (pintype "bidirectional"))
      (node (ref "U$20") (pin "7") (pinfunction "VIOUT_7") (pintype "bidirectional"))
    )
    (net (code "11") (name "AUX_P-SIG") (class "Default")
      (node (ref "U$1") (pin "11") (pinfunction "SCK_11") (pintype "bidirectional"))
      (node (ref "U$13") (pin "4") (pinfunction "IN_4") (pintype "bidirectional"))
    )
    (net (code "12") (name "BUZZ_BUZZ_MOTHERFUCKER") (class "Default")
      (node (ref "SG1") (pin "-") (pinfunction "2_-") (pintype "passive"))
      (node (ref "U$1") (pin "8") (pinfunction "D11~{}_8") (pintype "bidirectional"))
    )
    (net (code "13") (name "CRIT-IMEAS") (class "Default")
      (node (ref "Q5") (pin "7") (pinfunction "VIOUT_7") (pintype "bidirectional"))
      (node (ref "U$1") (pin "1") (pinfunction "D4/A6_1") (pintype "bidirectional"))
    )
    (net (code "14") (name "GND") (class "Default")
      (node (ref "12V-AUX") (pin "L1") (pinfunction "L_L1") (pintype "bidirectional"))
      (node (ref "12V-AUX") (pin "L2") (pinfunction "L_L2") (pintype "bidirectional"))
      (node (ref "12V-CRIT") (pin "L") (pinfunction "L_L") (pintype "bidirectional"))
      (node (ref "5V-EXT") (pin "L") (pinfunction "L_L") (pintype "bidirectional"))
      (node (ref "5V-INT") (pin "L") (pinfunction "L_L") (pintype "bidirectional"))
      (node (ref "ARM_P") (pin "L") (pinfunction "L_L") (pintype "bidirectional"))
      (node (ref "AUX_P") (pin "L1") (pinfunction "L_L1") (pintype "bidirectional"))
      (node (ref "AUX_P") (pin "L2") (pinfunction "L_L2") (pintype "bidirectional"))
      (node (ref "BATT-NEG") (pin "P$1") (pinfunction "P$1_P$1") (pintype "bidirectional"))
      (node (ref "C1") (pin "-") (pinfunction "-_-") (pintype "passive"))
      (node (ref "C10") (pin "1") (pinfunction "1_1") (pintype "passive"))
      (node (ref "C11") (pin "2") (pinfunction "2_2") (pintype "passive"))
      (node (ref "C12") (pin "2") (pinfunction "2_2") (pintype "passive"))
      (node (ref "C13") (pin "1") (pinfunction "1_1") (pintype "passive"))
      (node (ref "C14") (pin "1") (pinfunction "1_1") (pintype "passive"))
      (node (ref "C15") (pin "1") (pinfunction "1_1") (pintype "passive"))
      (node (ref "C16") (pin "1") (pinfunction "1_1") (pintype "passive"))
      (node (ref "C17") (pin "2") (pinfunction "2_2") (pintype "passive"))
      (node (ref "C18") (pin "2") (pinfunction "2_2") (pintype "passive"))
      (node (ref "C19") (pin "2") (pinfunction "2_2") (pintype "passive"))
      (node (ref "C2") (pin "-") (pinfunction "-_-") (pintype "passive"))
      (node (ref "C20") (pin "2") (pinfunction "2_2") (pintype "passive"))
      (node (ref "C21") (pin "-") (pinfunction "-_-") (pintype "passive"))
      (node (ref "C22") (pin "-") (pinfunction "-_-") (pintype "passive"))
      (node (ref "C23") (pin "1") (pinfunction "1_1") (pintype "passive"))
      (node (ref "C24") (pin "1") (pinfunction "1_1") (pintype "passive"))
      (node (ref "C25") (pin "1") (pinfunction "1_1") (pintype "passive"))
      (node (ref "C26") (pin "1") (pinfunction "1_1") (pintype "passive"))
      (node (ref "C27") (pin "2") (pinfunction "2_2") (pintype "passive"))
      (node (ref "C28") (pin "1") (pinfunction "1_1") (pintype "passive"))
      (node (ref "C29") (pin "1") (pinfunction "1_1") (pintype "passive"))
      (node (ref "C3") (pin "-") (pinfunction "-_-") (pintype "passive"))
      (node (ref "C30") (pin "1") (pinfunction "1_1") (pintype "passive"))
      (node (ref "C31") (pin "2") (pinfunction "2_2") (pintype "passive"))
      (node (ref "C32") (pin "1") (pinfunction "1_1") (pintype "passive"))
      (node (ref "C33") (pin "1") (pinfunction "1_1") (pintype "passive"))
      (node (ref "C34") (pin "1") (pinfunction "1_1") (pintype "passive"))
      (node (ref "C35") (pin "2") (pinfunction "2_2") (pintype "passive"))
      (node (ref "C36") (pin "1") (pinfunction "1_1") (pintype "passive"))
      (node (ref "C37") (pin "2") (pinfunction "2_2") (pintype "passive"))
      (node (ref "C38") (pin "2") (pinfunction "2_2") (pintype "passive"))
      (node (ref "C39") (pin "1") (pinfunction "1_1") (pintype "passive"))
      (node (ref "C4") (pin "-") (pinfunction "-_-") (pintype "passive"))
      (node (ref "C40") (pin "2") (pinfunction "2_2") (pintype "passive"))
      (node (ref "C41") (pin "1") (pinfunction "1_1") (pintype "passive"))
      (node (ref "C42") (pin "2") (pinfunction "2_2") (pintype "passive"))
      (node (ref "C43") (pin "2") (pinfunction "2_2") (pintype "passive"))
      (node (ref "C44") (pin "2") (pinfunction "2_2") (pintype "passive"))
      (node (ref "C45") (pin "-") (pinfunction "-_-") (pintype "passive"))
      (node (ref "C5") (pin "1") (pinfunction "1_1") (pintype "passive"))
      (node (ref "C6") (pin "1") (pinfunction "1_1") (pintype "passive"))
      (node (ref "C7") (pin "2") (pinfunction "2_2") (pintype "passive"))
      (node (ref "C8") (pin "2") (pinfunction "2_2") (pintype "passive"))
      (node (ref "C9") (pin "2") (pinfunction "2_2") (pintype "passive"))
      (node (ref "D1") (pin "A") (pinfunction "A_A") (pintype "passive"))
      (node (ref "D2") (pin "A") (pinfunction "A_A") (pintype "passive"))
      (node (ref "DOOKU-12V-CRIT") (pin "1") (pinfunction "GND_1") (pintype "bidirectional"))
      (node (ref "DOOKU-12V-CRIT") (pin "7") (pinfunction "GND1_7") (pintype "bidirectional"))
      (node (ref "LED1") (pin "C") (pinfunction "C_C") (pintype "passive"))
      (node (ref "LED10") (pin "C") (pinfunction "C_C") (pintype "passive"))
      (node (ref "LED11") (pin "C") (pinfunction "C_C") (pintype "passive"))
      (node (ref "LED12") (pin "C") (pinfunction "C_C") (pintype "passive"))
      (node (ref "LED13") (pin "C") (pinfunction "C_C") (pintype "passive"))
      (node (ref "LED14") (pin "C") (pinfunction "C_C") (pintype "passive"))
      (node (ref "LED2") (pin "C") (pinfunction "C_C") (pintype "passive"))
      (node (ref "LED3") (pin "C") (pinfunction "C_C") (pintype "passive"))
      (node (ref "LED4") (pin "C") (pinfunction "C_C") (pintype "passive"))
      (node (ref "LED5") (pin "C") (pinfunction "C_C") (pintype "passive"))
      (node (ref "LED6") (pin "C") (pinfunction "C_C") (pintype "passive"))
      (node (ref "LED7") (pin "C") (pinfunction "C_C") (pintype "passive"))
      (node (ref "LED8") (pin "C") (pinfunction "C_C") (pintype "passive"))
      (node (ref "LED9") (pin "C") (pinfunction "C_C") (pintype "passive"))
      (node (ref "MOTOR_1") (pin "L1") (pinfunction "L_L1") (pintype "bidirectional"))
      (node (ref "MOTOR_1") (pin "L2") (pinfunction "L_L2") (pintype "bidirectional"))
      (node (ref "MOTOR_2") (pin "L1") (pinfunction "L_L1") (pintype "bidirectional"))
      (node (ref "MOTOR_2") (pin "L2") (pinfunction "L_L2") (pintype "bidirectional"))
      (node (ref "MOTOR_3") (pin "L1") (pinfunction "L_L1") (pintype "bidirectional"))
      (node (ref "MOTOR_3") (pin "L2") (pinfunction "L_L2") (pintype "bidirectional"))
      (node (ref "MOTOR_4") (pin "L1") (pinfunction "L_L1") (pintype "bidirectional"))
      (node (ref "MOTOR_4") (pin "L2") (pinfunction "L_L2") (pintype "bidirectional"))
      (node (ref "MOTOR_5") (pin "L1") (pinfunction "L_L1") (pintype "bidirectional"))
      (node (ref "MOTOR_5") (pin "L2") (pinfunction "L_L2") (pintype "bidirectional"))
      (node (ref "MOTOR_6") (pin "L1") (pinfunction "L_L1") (pintype "bidirectional"))
      (node (ref "MOTOR_6") (pin "L2") (pinfunction "L_L2") (pintype "bidirectional"))
      (node (ref "OKI-78SR-5/1.5-W36H") (pin "2") (pinfunction "GND_2") (pintype "bidirectional"))
      (node (ref "PALPATINE-12V") (pin "3") (pinfunction "-VIN_3") (pintype "bidirectional"))
      (node (ref "PALPATINE-12V") (pin "4") (pinfunction "-VOUT_4") (pintype "bidirectional"))
      (node (ref "Q1") (pin "5") (pinfunction "GND_5") (pintype "bidirectional"))
      (node (ref "Q12") (pin "2") (pinfunction "S_2") (pintype "passive"))
      (node (ref "Q4") (pin "5") (pinfunction "GND_5") (pintype "bidirectional"))
      (node (ref "Q5") (pin "5") (pinfunction "GND_5") (pintype "bidirectional"))
      (node (ref "R4") (pin "1") (pinfunction "1_1") (pintype "passive"))
      (node (ref "R7") (pin "1") (pinfunction "1_1") (pintype "passive"))
      (node (ref "R8") (pin "1") (pinfunction "1_1") (pintype "passive"))
      (node (ref "SG1") (pin "+") (pinfunction "1_+") (pintype "passive"))
      (node (ref "SIDEOUS-12V") (pin "3") (pinfunction "-VIN_3") (pintype "bidirectional"))
      (node (ref "SIDEOUS-12V") (pin "4") (pinfunction "-VOUT_4") (pintype "bidirectional"))
      (node (ref "U$1") (pin "15") (pinfunction "GND_15") (pintype "bidirectional"))
      (node (ref "U$1") (pin "17") (pinfunction "GND_17") (pintype "bidirectional"))
      (node (ref "U$10") (pin "1") (pinfunction "GND_1") (pintype "bidirectional"))
      (node (ref "U$11") (pin "1") (pinfunction "GND_1") (pintype "bidirectional"))
      (node (ref "U$12") (pin "1") (pinfunction "GND_1") (pintype "bidirectional"))
      (node (ref "U$13") (pin "1") (pinfunction "GND_1") (pintype "bidirectional"))
      (node (ref "U$14") (pin "5") (pinfunction "GND_5") (pintype "bidirectional"))
      (node (ref "U$15") (pin "5") (pinfunction "GND_5") (pintype "bidirectional"))
      (node (ref "U$16") (pin "5") (pinfunction "GND_5") (pintype "bidirectional"))
      (node (ref "U$17") (pin "5") (pinfunction "GND_5") (pintype "bidirectional"))
      (node (ref "U$18") (pin "5") (pinfunction "GND_5") (pintype "bidirectional"))
      (node (ref "U$19") (pin "5") (pinfunction "GND_5") (pintype "bidirectional"))
      (node (ref "U$2") (pin "2") (pinfunction "A_2") (pintype "passive"))
      (node (ref "U$20") (pin "5") (pinfunction "GND_5") (pintype "bidirectional"))
      (node (ref "U$21") (pin "5") (pinfunction "GND_5") (pintype "bidirectional"))
      (node (ref "U$3") (pin "GND") (pinfunction "GND_GND") (pintype "bidirectional"))
      (node (ref "U$4") (pin "7") (pinfunction "7_7") (pintype "bidirectional"))
      (node (ref "U$4") (pin "8") (pinfunction "8_8") (pintype "bidirectional"))
      (node (ref "U$5") (pin "2") (pinfunction "A_2") (pintype "passive"))
      (node (ref "U$6") (pin "1") (pinfunction "GND_1") (pintype "bidirectional"))
      (node (ref "U$7") (pin "1") (pinfunction "GND_1") (pintype "bidirectional"))
      (node (ref "U$8") (pin "1") (pinfunction "GND_1") (pintype "bidirectional"))
      (node (ref "U$9") (pin "1") (pinfunction "GND_1") (pintype "bidirectional"))
      (node (ref "VADER-5V-EXT") (pin "1") (pinfunction "GND_1") (pintype "bidirectional"))
      (node (ref "VADER-5V-EXT") (pin "7") (pinfunction "GND1_7") (pintype "bidirectional"))
    )
    (net (code "15") (name "INFO_LED_1") (class "Default")
      (node (ref "R1") (pin "1") (pinfunction "1_1") (pintype "passive"))
      (node (ref "U$1") (pin "9") (pinfunction "MISO_9") (pintype "bidirectional"))
    )
    (net (code "16") (name "INFO_LED_2") (class "Default")
      (node (ref "R2") (pin "1") (pinfunction "1_1") (pintype "passive"))
      (node (ref "U$1") (pin "10") (pinfunction "MOSI_10") (pintype "bidirectional"))
    )
    (net (code "17") (name "M1-IMEAS") (class "Default")
      (node (ref "U$1") (pin "21") (pinfunction "A3_21") (pintype "bidirectional"))
      (node (ref "U$14") (pin "7") (pinfunction "VIOUT_7") (pintype "bidirectional"))
    )
    (net (code "18") (name "M1-SIG") (class "Default")
      (node (ref "U$1") (pin "25") (pinfunction "PE2_25") (pintype "bidirectional"))
      (node (ref "U$6") (pin "4") (pinfunction "IN_4") (pintype "bidirectional"))
    )
    (net (code "19") (name "M2-IMEAS") (class "Default")
      (node (ref "U$1") (pin "22") (pinfunction "A2_22") (pintype "bidirectional"))
      (node (ref "U$15") (pin "7") (pinfunction "VIOUT_7") (pintype "bidirectional"))
    )
    (net (code "20") (name "M2-SIG") (class "Default")
      (node (ref "U$1") (pin "26") (pinfunction "D13~{}_26") (pintype "bidirectional"))
      (node (ref "U$7") (pin "4") (pinfunction "IN_4") (pintype "bidirectional"))
    )
    (net (code "21") (name "M3-IMEAS") (class "Default")
      (node (ref "U$1") (pin "23") (pinfunction "A1_23") (pintype "bidirectional"))
      (node (ref "U$19") (pin "7") (pinfunction "VIOUT_7") (pintype "bidirectional"))
    )
    (net (code "22") (name "M3-SIG") (class "Default")
      (node (ref "U$1") (pin "27") (pinfunction "D5~{}_27") (pintype "bidirectional"))
      (node (ref "U$8") (pin "4") (pinfunction "IN_4") (pintype "bidirectional"))
    )
    (net (code "23") (name "M4-IMEAS") (class "Default")
      (node (ref "U$1") (pin "24") (pinfunction "A0_24") (pintype "bidirectional"))
      (node (ref "U$18") (pin "7") (pinfunction "VIOUT_7") (pintype "bidirectional"))
    )
    (net (code "24") (name "M4-SIG") (class "Default")
      (node (ref "U$1") (pin "2") (pinfunction "PD5_2") (pintype "bidirectional"))
      (node (ref "U$9") (pin "4") (pinfunction "IN_4") (pintype "bidirectional"))
    )
    (net (code "25") (name "M5-IMEAS") (class "Default")
      (node (ref "U$1") (pin "28") (pinfunction "D10~{/A10}_28") (pintype "bidirectional"))
      (node (ref "U$17") (pin "7") (pinfunction "VIOUT_7") (pintype "bidirectional"))
    )
    (net (code "26") (name "M5-SIG") (class "Default")
      (node (ref "U$1") (pin "5") (pinfunction "D2_5") (pintype "bidirectional"))
      (node (ref "U$10") (pin "4") (pinfunction "IN_4") (pintype "bidirectional"))
    )
    (net (code "27") (name "M6-IMEAS") (class "Default")
      (node (ref "U$1") (pin "29") (pinfunction "D9~{/A9}_29") (pintype "bidirectional"))
      (node (ref "U$16") (pin "7") (pinfunction "VIOUT_7") (pintype "bidirectional"))
    )
    (net (code "28") (name "M6-SIG") (class "Default")
      (node (ref "U$1") (pin "6") (pinfunction "D3~{}_6") (pintype "bidirectional"))
      (node (ref "U$11") (pin "4") (pinfunction "IN_4") (pintype "bidirectional"))
    )
    (net (code "29") (name "Net-(DOOKU-12V-CRIT-ADJUST)") (class "Default")
      (node (ref "DOOKU-12V-CRIT") (pin "4") (pinfunction "ADJUST_4") (pintype "bidirectional"))
      (node (ref "R7") (pin "2") (pinfunction "2_2") (pintype "passive"))
    )
    (net (code "30") (name "Net-(DOOKU-12V-CRIT-SENSE)") (class "Default")
      (node (ref "C21") (pin "+") (pinfunction "+_+") (pintype "passive"))
      (node (ref "DOOKU-12V-CRIT") (pin "5") (pinfunction "SENSE_5") (pintype "bidirectional"))
      (node (ref "DOOKU-12V-CRIT") (pin "6") (pinfunction "VOUT_6") (pintype "bidirectional"))
      (node (ref "L1") (pin "1") (pinfunction "1_1") (pintype "bidirectional"))
      (node (ref "L1") (pin "2") (pinfunction "2_2") (pintype "bidirectional"))
      (node (ref "L1") (pin "3") (pinfunction "3_3") (pintype "bidirectional"))
      (node (ref "L1") (pin "4") (pinfunction "4_4") (pintype "bidirectional"))
    )
    (net (code "31") (name "Net-(DOOKU-12V-CRIT-VIN)") (class "Default")
      (node (ref "C14") (pin "2") (pinfunction "2_2") (pintype "passive"))
      (node (ref "DOOKU-12V-CRIT") (pin "2") (pinfunction "VIN_2") (pintype "bidirectional"))
      (node (ref "L5") (pin "5") (pinfunction "5_5") (pintype "bidirectional"))
      (node (ref "L5") (pin "6") (pinfunction "6_6") (pintype "bidirectional"))
      (node (ref "L5") (pin "7") (pinfunction "7_7") (pintype "bidirectional"))
      (node (ref "L5") (pin "8") (pinfunction "8_8") (pintype "bidirectional"))
    )
    (net (code "32") (name "Net-(LED1-PadA)") (class "Default")
      (node (ref "LED1") (pin "A") (pinfunction "A_A") (pintype "passive"))
      (node (ref "R9") (pin "2") (pinfunction "2_2") (pintype "passive"))
    )
    (net (code "33") (name "Net-(LED2-PadA)") (class "Default")
      (node (ref "LED2") (pin "A") (pinfunction "A_A") (pintype "passive"))
      (node (ref "R10") (pin "2") (pinfunction "2_2") (pintype "passive"))
    )
    (net (code "34") (name "Net-(LED3-PadA)") (class "Default")
      (node (ref "LED3") (pin "A") (pinfunction "A_A") (pintype "passive"))
      (node (ref "R11") (pin "2") (pinfunction "2_2") (pintype "passive"))
    )
    (net (code "35") (name "Net-(LED4-PadA)") (class "Default")
      (node (ref "LED4") (pin "A") (pinfunction "A_A") (pintype "passive"))
      (node (ref "R12") (pin "2") (pinfunction "2_2") (pintype "passive"))
    )
    (net (code "36") (name "Net-(LED5-PadA)") (class "Default")
      (node (ref "LED5") (pin "A") (pinfunction "A_A") (pintype "passive"))
      (node (ref "R13") (pin "2") (pinfunction "2_2") (pintype "passive"))
    )
    (net (code "37") (name "Net-(LED6-PadA)") (class "Default")
      (node (ref "LED6") (pin "A") (pinfunction "A_A") (pintype "passive"))
      (node (ref "R16") (pin "2") (pinfunction "2_2") (pintype "passive"))
    )
    (net (code "38") (name "Net-(LED7-PadA)") (class "Default")
      (node (ref "LED7") (pin "A") (pinfunction "A_A") (pintype "passive"))
      (node (ref "R18") (pin "2") (pinfunction "2_2") (pintype "passive"))
    )
    (net (code "39") (name "Net-(LED8-PadA)") (class "Default")
      (node (ref "LED8") (pin "A") (pinfunction "A_A") (pintype "passive"))
      (node (ref "R20") (pin "2") (pinfunction "2_2") (pintype "passive"))
    )
    (net (code "40") (name "Net-(LED9-PadA)") (class "Default")
      (node (ref "LED9") (pin "A") (pinfunction "A_A") (pintype "passive"))
      (node (ref "R22") (pin "2") (pinfunction "2_2") (pintype "passive"))
    )
    (net (code "41") (name "Net-(LED10-PadA)") (class "Default")
      (node (ref "LED10") (pin "A") (pinfunction "A_A") (pintype "passive"))
      (node (ref "R24") (pin "2") (pinfunction "2_2") (pintype "passive"))
    )
    (net (code "42") (name "Net-(LED11-PadA)") (class "Default")
      (node (ref "LED11") (pin "A") (pinfunction "A_A") (pintype "passive"))
      (node (ref "R26") (pin "2") (pinfunction "2_2") (pintype "passive"))
    )
    (net (code "43") (name "Net-(LED12-PadA)") (class "Default")
      (node (ref "LED12") (pin "A") (pinfunction "A_A") (pintype "passive"))
      (node (ref "R28") (pin "2") (pinfunction "2_2") (pintype "passive"))
    )
    (net (code "44") (name "Net-(LED13-PadA)") (class "Default")
      (node (ref "LED13") (pin "A") (pinfunction "A_A") (pintype "passive"))
      (node (ref "R1") (pin "2") (pinfunction "2_2") (pintype "passive"))
    )
    (net (code "45") (name "Net-(LED14-PadA)") (class "Default")
      (node (ref "LED14") (pin "A") (pinfunction "A_A") (pintype "passive"))
      (node (ref "R2") (pin "2") (pinfunction "2_2") (pintype "passive"))
    )
    (net (code "46") (name "Net-(OKI-78SR-5/1.5-W36H-VO)") (class "Default")
      (node (ref "C17") (pin "1") (pinfunction "1_1") (pintype "passive"))
      (node (ref "L3") (pin "1") (pinfunction "1_1") (pintype "passive"))
      (node (ref "OKI-78SR-5/1.5-W36H") (pin "3") (pinfunction "VO_3") (pintype "bidirectional"))
    )
    (net (code "47") (name "Net-(PALPATINE-12V-+VIN)") (class "Default")
      (node (ref "L6") (pin "10") (pinfunction "10_10") (pintype "bidirectional"))
      (node (ref "L6") (pin "6") (pinfunction "6_6") (pintype "bidirectional"))
      (node (ref "L6") (pin "7") (pinfunction "7_7") (pintype "bidirectional"))
      (node (ref "L6") (pin "8") (pinfunction "8_8") (pintype "bidirectional"))
      (node (ref "L6") (pin "9") (pinfunction "9_9") (pintype "bidirectional"))
      (node (ref "PALPATINE-12V") (pin "1") (pinfunction "+VIN_1") (pintype "bidirectional"))
    )
    (net (code "48") (name "Net-(PALPATINE-12V-+VOUT)") (class "Default")
      (node (ref "C19") (pin "1") (pinfunction "1_1") (pintype "passive"))
      (node (ref "C20") (pin "1") (pinfunction "1_1") (pintype "passive"))
      (node (ref "C45") (pin "+") (pinfunction "+_+") (pintype "passive"))
      (node (ref "PALPATINE-12V") (pin "8") (pinfunction "+VOUT_8") (pintype "bidirectional"))
      (node (ref "SIDEOUS-12V") (pin "8") (pinfunction "+VOUT_8") (pintype "bidirectional"))
      (node (ref "U$21") (pin "1") (pinfunction "IP+_1") (pintype "bidirectional"))
    )
    (net (code "49") (name "Net-(PALPATINE-12V-REMOTE)") (class "Default")
      (node (ref "PALPATINE-12V") (pin "2") (pinfunction "REMOTE_2") (pintype "bidirectional"))
      (node (ref "Q12") (pin "3") (pinfunction "D_3") (pintype "passive"))
      (node (ref "SIDEOUS-12V") (pin "2") (pinfunction "REMOTE_2") (pintype "bidirectional"))
    )
    (net (code "50") (name "Net-(Q1-IP-)") (class "Default")
      (node (ref "C34") (pin "2") (pinfunction "2_2") (pintype "passive"))
      (node (ref "Q1") (pin "4") (pinfunction "IP-_4") (pintype "bidirectional"))
      (node (ref "Q18") (pin "2") (pinfunction "D_2") (pintype "bidirectional"))
      (node (ref "Q18") (pin "4") (pinfunction "D_4") (pintype "bidirectional"))
      (node (ref "U$12") (pin "6") (pinfunction "SENSE_6") (pintype "bidirectional"))
      (node (ref "U$12") (pin "8") (pinfunction "V+_8") (pintype "bidirectional"))
    )
    (net (code "51") (name "Net-(Q4-IP+)") (class "Default")
      (node (ref "C11") (pin "1") (pinfunction "1_1") (pintype "passive"))
      (node (ref "L4") (pin "5") (pinfunction "5_5") (pintype "bidirectional"))
      (node (ref "L4") (pin "6") (pinfunction "6_6") (pintype "bidirectional"))
      (node (ref "L4") (pin "7") (pinfunction "7_7") (pintype "bidirectional"))
      (node (ref "L4") (pin "8") (pinfunction "8_8") (pintype "bidirectional"))
      (node (ref "Q4") (pin "1") (pinfunction "IP+_1") (pintype "bidirectional"))
      (node (ref "U$2") (pin "1") (pinfunction "C_1") (pintype "passive"))
    )
    (net (code "52") (name "Net-(Q5-IP-)") (class "Default")
      (node (ref "C9") (pin "1") (pinfunction "1_1") (pintype "passive"))
      (node (ref "L1") (pin "5") (pinfunction "5_5") (pintype "bidirectional"))
      (node (ref "L1") (pin "6") (pinfunction "6_6") (pintype "bidirectional"))
      (node (ref "L1") (pin "7") (pinfunction "7_7") (pintype "bidirectional"))
      (node (ref "L1") (pin "8") (pinfunction "8_8") (pintype "bidirectional"))
      (node (ref "Q5") (pin "4") (pinfunction "IP-_4") (pintype "bidirectional"))
      (node (ref "U$5") (pin "1") (pinfunction "C_1") (pintype "passive"))
    )
    (net (code "53") (name "Net-(Q6-D)") (class "Default")
      (node (ref "C16") (pin "2") (pinfunction "2_2") (pintype "passive"))
      (node (ref "Q6") (pin "TAB") (pinfunction "D_TAB") (pintype "bidirectional"))
      (node (ref "U$14") (pin "4") (pinfunction "IP-_4") (pintype "bidirectional"))
      (node (ref "U$6") (pin "6") (pinfunction "SENSE_6") (pintype "bidirectional"))
      (node (ref "U$6") (pin "8") (pinfunction "V+_8") (pintype "bidirectional"))
    )
    (net (code "54") (name "Net-(Q6-G)") (class "Default")
      (node (ref "Q6") (pin "1") (pinfunction "G_1") (pintype "bidirectional"))
      (node (ref "U$6") (pin "5") (pinfunction "GATE_5") (pintype "bidirectional"))
    )
    (net (code "55") (name "Net-(Q6-S)") (class "Default")
      (node (ref "MOTOR_1") (pin "R1") (pinfunction "R_R1") (pintype "bidirectional"))
      (node (ref "MOTOR_1") (pin "R2") (pinfunction "R_R2") (pintype "bidirectional"))
      (node (ref "Q6") (pin "2") (pinfunction "S_2") (pintype "bidirectional"))
      (node (ref "R9") (pin "1") (pinfunction "1_1") (pintype "passive"))
    )
    (net (code "56") (name "Net-(Q7-D)") (class "Default")
      (node (ref "C24") (pin "2") (pinfunction "2_2") (pintype "passive"))
      (node (ref "Q7") (pin "TAB") (pinfunction "D_TAB") (pintype "bidirectional"))
      (node (ref "U$15") (pin "4") (pinfunction "IP-_4") (pintype "bidirectional"))
      (node (ref "U$7") (pin "6") (pinfunction "SENSE_6") (pintype "bidirectional"))
      (node (ref "U$7") (pin "8") (pinfunction "V+_8") (pintype "bidirectional"))
    )
    (net (code "57") (name "Net-(Q7-G)") (class "Default")
      (node (ref "Q7") (pin "1") (pinfunction "G_1") (pintype "bidirectional"))
      (node (ref "U$7") (pin "5") (pinfunction "GATE_5") (pintype "bidirectional"))
    )
    (net (code "58") (name "Net-(Q7-S)") (class "Default")
      (node (ref "MOTOR_2") (pin "R1") (pinfunction "R_R1") (pintype "bidirectional"))
      (node (ref "MOTOR_2") (pin "R2") (pinfunction "R_R2") (pintype "bidirectional"))
      (node (ref "Q7") (pin "2") (pinfunction "S_2") (pintype "bidirectional"))
      (node (ref "R16") (pin "1") (pinfunction "1_1") (pintype "passive"))
    )
    (net (code "59") (name "Net-(Q9-D)") (class "Default")
      (node (ref "C26") (pin "2") (pinfunction "2_2") (pintype "passive"))
      (node (ref "Q9") (pin "TAB") (pinfunction "D_TAB") (pintype "bidirectional"))
      (node (ref "U$19") (pin "4") (pinfunction "IP-_4") (pintype "bidirectional"))
      (node (ref "U$8") (pin "6") (pinfunction "SENSE_6") (pintype "bidirectional"))
      (node (ref "U$8") (pin "8") (pinfunction "V+_8") (pintype "bidirectional"))
    )
    (net (code "60") (name "Net-(Q9-G)") (class "Default")
      (node (ref "Q9") (pin "1") (pinfunction "G_1") (pintype "bidirectional"))
      (node (ref "U$8") (pin "5") (pinfunction "GATE_5") (pintype "bidirectional"))
    )
    (net (code "61") (name "Net-(Q9-S)") (class "Default")
      (node (ref "MOTOR_3") (pin "R1") (pinfunction "R_R1") (pintype "bidirectional"))
      (node (ref "MOTOR_3") (pin "R2") (pinfunction "R_R2") (pintype "bidirectional"))
      (node (ref "Q9") (pin "2") (pinfunction "S_2") (pintype "bidirectional"))
      (node (ref "R18") (pin "1") (pinfunction "1_1") (pintype "passive"))
    )
    (net (code "62") (name "Net-(Q11-D)") (class "Default")
      (node (ref "C28") (pin "2") (pinfunction "2_2") (pintype "passive"))
      (node (ref "Q11") (pin "TAB") (pinfunction "D_TAB") (pintype "bidirectional"))
      (node (ref "U$18") (pin "4") (pinfunction "IP-_4") (pintype "bidirectional"))
      (node (ref "U$9") (pin "6") (pinfunction "SENSE_6") (pintype "bidirectional"))
      (node (ref "U$9") (pin "8") (pinfunction "V+_8") (pintype "bidirectional"))
    )
    (net (code "63") (name "Net-(Q11-G)") (class "Default")
      (node (ref "Q11") (pin "1") (pinfunction "G_1") (pintype "bidirectional"))
      (node (ref "U$9") (pin "5") (pinfunction "GATE_5") (pintype "bidirectional"))
    )
    (net (code "64") (name "Net-(Q11-S)") (class "Default")
      (node (ref "MOTOR_4") (pin "R1") (pinfunction "R_R1") (pintype "bidirectional"))
      (node (ref "MOTOR_4") (pin "R2") (pinfunction "R_R2") (pintype "bidirectional"))
      (node (ref "Q11") (pin "2") (pinfunction "S_2") (pintype "bidirectional"))
      (node (ref "R20") (pin "1") (pinfunction "1_1") (pintype "passive"))
    )
    (net (code "65") (name "Net-(Q12-G)") (class "Default")
      (node (ref "Q12") (pin "1") (pinfunction "G_1") (pintype "passive"))
      (node (ref "R15") (pin "1") (pinfunction "1_1") (pintype "passive"))
    )
    (net (code "66") (name "Net-(Q14-D)") (class "Default")
      (node (ref "C30") (pin "2") (pinfunction "2_2") (pintype "passive"))
      (node (ref "Q14") (pin "TAB") (pinfunction "D_TAB") (pintype "bidirectional"))
      (node (ref "U$10") (pin "6") (pinfunction "SENSE_6") (pintype "bidirectional"))
      (node (ref "U$10") (pin "8") (pinfunction "V+_8") (pintype "bidirectional"))
      (node (ref "U$17") (pin "4") (pinfunction "IP-_4") (pintype "bidirectional"))
    )
    (net (code "67") (name "Net-(Q14-G)") (class "Default")
      (node (ref "Q14") (pin "1") (pinfunction "G_1") (pintype "bidirectional"))
      (node (ref "U$10") (pin "5") (pinfunction "GATE_5") (pintype "bidirectional"))
    )
    (net (code "68") (name "Net-(Q14-S)") (class "Default")
      (node (ref "MOTOR_5") (pin "R1") (pinfunction "R_R1") (pintype "bidirectional"))
      (node (ref "MOTOR_5") (pin "R2") (pinfunction "R_R2") (pintype "bidirectional"))
      (node (ref "Q14") (pin "2") (pinfunction "S_2") (pintype "bidirectional"))
      (node (ref "R22") (pin "1") (pinfunction "1_1") (pintype "passive"))
    )
    (net (code "69") (name "Net-(Q16-D)") (class "Default")
      (node (ref "C32") (pin "2") (pinfunction "2_2") (pintype "passive"))
      (node (ref "Q16") (pin "TAB") (pinfunction "D_TAB") (pintype "bidirectional"))
      (node (ref "U$11") (pin "6") (pinfunction "SENSE_6") (pintype "bidirectional"))
      (node (ref "U$11") (pin "8") (pinfunction "V+_8") (pintype "bidirectional"))
      (node (ref "U$16") (pin "4") (pinfunction "IP-_4") (pintype "bidirectional"))
    )
    (net (code "70") (name "Net-(Q16-G)") (class "Default")
      (node (ref "Q16") (pin "1") (pinfunction "G_1") (pintype "bidirectional"))
      (node (ref "U$11") (pin "5") (pinfunction "GATE_5") (pintype "bidirectional"))
    )
    (net (code "71") (name "Net-(Q16-S)") (class "Default")
      (node (ref "MOTOR_6") (pin "R1") (pinfunction "R_R1") (pintype "bidirectional"))
      (node (ref "MOTOR_6") (pin "R2") (pinfunction "R_R2") (pintype "bidirectional"))
      (node (ref "Q16") (pin "2") (pinfunction "S_2") (pintype "bidirectional"))
      (node (ref "R24") (pin "1") (pinfunction "1_1") (pintype "passive"))
    )
    (net (code "72") (name "Net-(Q18-G)") (class "Default")
      (node (ref "Q18") (pin "1") (pinfunction "G_1") (pintype "bidirectional"))
      (node (ref "U$12") (pin "5") (pinfunction "GATE_5") (pintype "bidirectional"))
    )
    (net (code "73") (name "Net-(Q18-S)") (class "Default")
      (node (ref "ARM_P") (pin "R") (pinfunction "R_R") (pintype "bidirectional"))
      (node (ref "Q18") (pin "3") (pinfunction "S_3") (pintype "bidirectional"))
      (node (ref "R26") (pin "1") (pinfunction "1_1") (pintype "passive"))
    )
    (net (code "74") (name "Net-(Q20-D)") (class "Default")
      (node (ref "C36") (pin "2") (pinfunction "2_2") (pintype "passive"))
      (node (ref "Q20") (pin "TAB") (pinfunction "D_TAB") (pintype "bidirectional"))
      (node (ref "U$13") (pin "6") (pinfunction "SENSE_6") (pintype "bidirectional"))
      (node (ref "U$13") (pin "8") (pinfunction "V+_8") (pintype "bidirectional"))
      (node (ref "U$20") (pin "4") (pinfunction "IP-_4") (pintype "bidirectional"))
    )
    (net (code "75") (name "Net-(Q20-G)") (class "Default")
      (node (ref "Q20") (pin "1") (pinfunction "G_1") (pintype "bidirectional"))
      (node (ref "U$13") (pin "5") (pinfunction "GATE_5") (pintype "bidirectional"))
    )
    (net (code "76") (name "Net-(Q20-S)") (class "Default")
      (node (ref "AUX_P") (pin "R1") (pinfunction "R_R1") (pintype "bidirectional"))
      (node (ref "AUX_P") (pin "R2") (pinfunction "R_R2") (pintype "bidirectional"))
      (node (ref "Q20") (pin "2") (pinfunction "S_2") (pintype "bidirectional"))
      (node (ref "R28") (pin "1") (pinfunction "1_1") (pintype "passive"))
    )
    (net (code "77") (name "Net-(R5-Pad1)") (class "Default")
      (node (ref "R5") (pin "1") (pinfunction "1_1") (pintype "passive"))
      (node (ref "U$3") (pin "A") (pinfunction "A_A") (pintype "bidirectional"))
      (node (ref "U$4") (pin "3") (pinfunction "3_3") (pintype "bidirectional"))
    )
    (net (code "78") (name "Net-(R5-Pad2)") (class "Default")
      (node (ref "R5") (pin "2") (pinfunction "2_2") (pintype "passive"))
      (node (ref "U$3") (pin "B") (pinfunction "B_B") (pintype "bidirectional"))
      (node (ref "U$4") (pin "6") (pinfunction "6_6") (pintype "bidirectional"))
    )
    (net (code "79") (name "Net-(R6-Pad1)") (class "Default")
      (node (ref "R6") (pin "1") (pinfunction "1_1") (pintype "passive"))
      (node (ref "U$3") (pin "Z") (pinfunction "Z_Z") (pintype "bidirectional"))
      (node (ref "U$4") (pin "2") (pinfunction "2_2") (pintype "bidirectional"))
    )
    (net (code "80") (name "Net-(R6-Pad2)") (class "Default")
      (node (ref "R6") (pin "2") (pinfunction "2_2") (pintype "passive"))
      (node (ref "U$3") (pin "Y") (pinfunction "Y_Y") (pintype "bidirectional"))
      (node (ref "U$4") (pin "1") (pinfunction "1_1") (pintype "bidirectional"))
    )
    (net (code "81") (name "Net-(SIDEOUS-12V-+VIN)") (class "Default")
      (node (ref "L2") (pin "10") (pinfunction "10_10") (pintype "bidirectional"))
      (node (ref "L2") (pin "6") (pinfunction "6_6") (pintype "bidirectional"))
      (node (ref "L2") (pin "7") (pinfunction "7_7") (pintype "bidirectional"))
      (node (ref "L2") (pin "8") (pinfunction "8_8") (pintype "bidirectional"))
      (node (ref "L2") (pin "9") (pinfunction "9_9") (pintype "bidirectional"))
      (node (ref "SIDEOUS-12V") (pin "1") (pinfunction "+VIN_1") (pintype "bidirectional"))
    )
    (net (code "82") (name "Net-(U$1-D0{slash}RX)") (class "Default")
      (node (ref "U$1") (pin "4") (pinfunction "D0/RX_4") (pintype "bidirectional"))
      (node (ref "U$3") (pin "RO") (pinfunction "R0_RO") (pintype "bidirectional"))
    )
    (net (code "83") (name "Net-(U$1-D1{slash}TX)") (class "Default")
      (node (ref "U$1") (pin "3") (pinfunction "D1/TX_3") (pintype "bidirectional"))
      (node (ref "U$3") (pin "DI") (pinfunction "DI_DI") (pintype "bidirectional"))
    )
    (net (code "84") (name "Net-(U$14-FILTER)") (class "Default")
      (node (ref "C37") (pin "1") (pinfunction "1_1") (pintype "passive"))
      (node (ref "U$14") (pin "6") (pinfunction "FILTER_6") (pintype "bidirectional"))
    )
    (net (code "85") (name "Net-(U$15-FILTER)") (class "Default")
      (node (ref "C38") (pin "1") (pinfunction "1_1") (pintype "passive"))
      (node (ref "U$15") (pin "6") (pinfunction "FILTER_6") (pintype "bidirectional"))
    )
    (net (code "86") (name "Net-(U$16-FILTER)") (class "Default")
      (node (ref "C27") (pin "1") (pinfunction "1_1") (pintype "passive"))
      (node (ref "U$16") (pin "6") (pinfunction "FILTER_6") (pintype "bidirectional"))
    )
    (net (code "87") (name "Net-(U$17-FILTER)") (class "Default")
      (node (ref "C31") (pin "1") (pinfunction "1_1") (pintype "passive"))
      (node (ref "U$17") (pin "6") (pinfunction "FILTER_6") (pintype "bidirectional"))
    )
    (net (code "88") (name "Net-(U$18-FILTER)") (class "Default")
      (node (ref "C35") (pin "1") (pinfunction "1_1") (pintype "passive"))
      (node (ref "U$18") (pin "6") (pinfunction "FILTER_6") (pintype "bidirectional"))
    )
    (net (code "89") (name "Net-(U$19-FILTER)") (class "Default")
      (node (ref "C40") (pin "1") (pinfunction "1_1") (pintype "passive"))
      (node (ref "U$19") (pin "6") (pinfunction "FILTER_6") (pintype "bidirectional"))
    )
    (net (code "90") (name "Net-(U$20-FILTER)") (class "Default")
      (node (ref "C42") (pin "1") (pinfunction "1_1") (pintype "passive"))
      (node (ref "U$20") (pin "6") (pinfunction "FILTER_6") (pintype "bidirectional"))
    )
    (net (code "91") (name "Net-(U$21-FILTER)") (class "Default")
      (node (ref "C43") (pin "1") (pinfunction "1_1") (pintype "passive"))
      (node (ref "U$21") (pin "6") (pinfunction "FILTER_6") (pintype "bidirectional"))
    )
    (net (code "92") (name "Net-(VADER-5V-EXT-ADJUST)") (class "Default")
      (node (ref "R8") (pin "2") (pinfunction "2_2") (pintype "passive"))
      (node (ref "VADER-5V-EXT") (pin "4") (pinfunction "ADJUST_4") (pintype "bidirectional"))
    )
    (net (code "93") (name "Net-(VADER-5V-EXT-SENSE)") (class "Default")
      (node (ref "C22") (pin "+") (pinfunction "+_+") (pintype "passive"))
      (node (ref "L4") (pin "1") (pinfunction "1_1") (pintype "bidirectional"))
      (node (ref "L4") (pin "2") (pinfunction "2_2") (pintype "bidirectional"))
      (node (ref "L4") (pin "3") (pinfunction "3_3") (pintype "bidirectional"))
      (node (ref "L4") (pin "4") (pinfunction "4_4") (pintype "bidirectional"))
      (node (ref "VADER-5V-EXT") (pin "5") (pinfunction "SENSE_5") (pintype "bidirectional"))
      (node (ref "VADER-5V-EXT") (pin "6") (pinfunction "VOUT_6") (pintype "bidirectional"))
    )
    (net (code "94") (name "Net-(VADER-5V-EXT-VIN)") (class "Default")
      (node (ref "C13") (pin "2") (pinfunction "2_2") (pintype "passive"))
      (node (ref "L8") (pin "5") (pinfunction "5_5") (pintype "bidirectional"))
      (node (ref "L8") (pin "6") (pinfunction "6_6") (pintype "bidirectional"))
      (node (ref "L8") (pin "7") (pinfunction "7_7") (pintype "bidirectional"))
      (node (ref "L8") (pin "8") (pinfunction "8_8") (pintype "bidirectional"))
      (node (ref "VADER-5V-EXT") (pin "2") (pinfunction "VIN_2") (pintype "bidirectional"))
    )
    (net (code "95") (name "PRIMARY-VMEAS") (class "Default")
      (node (ref "R3") (pin "1") (pinfunction "1_1") (pintype "passive"))
      (node (ref "R4") (pin "2") (pinfunction "2_2") (pintype "passive"))
      (node (ref "U$1") (pin "19") (pinfunction "A5_19") (pintype "bidirectional"))
    )
    (net (code "96") (name "V_BATT") (class "Default")
      (node (ref "BATT-POS") (pin "P$1") (pinfunction "P$1_P$1") (pintype "bidirectional"))
      (node (ref "C1") (pin "+") (pinfunction "+_+") (pintype "passive"))
      (node (ref "C10") (pin "2") (pinfunction "2_2") (pintype "passive"))
      (node (ref "C15") (pin "2") (pinfunction "2_2") (pintype "passive"))
      (node (ref "C2") (pin "+") (pinfunction "+_+") (pintype "passive"))
      (node (ref "C3") (pin "+") (pinfunction "+_+") (pintype "passive"))
      (node (ref "C4") (pin "+") (pinfunction "+_+") (pintype "passive"))
      (node (ref "D1") (pin "C") (pinfunction "C_C") (pintype "passive"))
      (node (ref "D2") (pin "C") (pinfunction "C_C") (pintype "passive"))
      (node (ref "L2") (pin "1") (pinfunction "1_1") (pintype "bidirectional"))
      (node (ref "L2") (pin "2") (pinfunction "2_2") (pintype "bidirectional"))
      (node (ref "L2") (pin "3") (pinfunction "3_3") (pintype "bidirectional"))
      (node (ref "L2") (pin "4") (pinfunction "4_4") (pintype "bidirectional"))
      (node (ref "L2") (pin "5") (pinfunction "5_5") (pintype "bidirectional"))
      (node (ref "L5") (pin "1") (pinfunction "1_1") (pintype "bidirectional"))
      (node (ref "L5") (pin "2") (pinfunction "2_2") (pintype "bidirectional"))
      (node (ref "L5") (pin "3") (pinfunction "3_3") (pintype "bidirectional"))
      (node (ref "L5") (pin "4") (pinfunction "4_4") (pintype "bidirectional"))
      (node (ref "L6") (pin "1") (pinfunction "1_1") (pintype "bidirectional"))
      (node (ref "L6") (pin "2") (pinfunction "2_2") (pintype "bidirectional"))
      (node (ref "L6") (pin "3") (pinfunction "3_3") (pintype "bidirectional"))
      (node (ref "L6") (pin "4") (pinfunction "4_4") (pintype "bidirectional"))
      (node (ref "L6") (pin "5") (pinfunction "5_5") (pintype "bidirectional"))
      (node (ref "L8") (pin "1") (pinfunction "1_1") (pintype "bidirectional"))
      (node (ref "L8") (pin "2") (pinfunction "2_2") (pintype "bidirectional"))
      (node (ref "L8") (pin "3") (pinfunction "3_3") (pintype "bidirectional"))
      (node (ref "L8") (pin "4") (pinfunction "4_4") (pintype "bidirectional"))
      (node (ref "Q1") (pin "1") (pinfunction "IP+_1") (pintype "bidirectional"))
      (node (ref "R3") (pin "2") (pinfunction "2_2") (pintype "passive"))
      (node (ref "U$14") (pin "1") (pinfunction "IP+_1") (pintype "bidirectional"))
      (node (ref "U$15") (pin "1") (pinfunction "IP+_1") (pintype "bidirectional"))
      (node (ref "U$16") (pin "1") (pinfunction "IP+_1") (pintype "bidirectional"))
      (node (ref "U$17") (pin "1") (pinfunction "IP+_1") (pintype "bidirectional"))
      (node (ref "U$18") (pin "1") (pinfunction "IP+_1") (pintype "bidirectional"))
      (node (ref "U$19") (pin "1") (pinfunction "IP+_1") (pintype "bidirectional"))
      (node (ref "U$20") (pin "1") (pinfunction "IP+_1") (pintype "bidirectional"))
    )
    (net (code "97") (name "unconnected-(DOOKU-12V-CRIT-INHIBIT-Pad3)") (class "Default")
      (node (ref "DOOKU-12V-CRIT") (pin "3") (pinfunction "INHIBIT_3") (pintype "bidirectional"))
    )
    (net (code "98") (name "unconnected-(Q1-FAULT-Pad6)") (class "Default")
      (node (ref "Q1") (pin "6") (pinfunction "FAULT_6") (pintype "bidirectional"))
    )
    (net (code "99") (name "unconnected-(Q4-FAULT-Pad6)") (class "Default")
      (node (ref "Q4") (pin "6") (pinfunction "FAULT_6") (pintype "bidirectional"))
    )
    (net (code "100") (name "unconnected-(Q5-FAULT-Pad6)") (class "Default")
      (node (ref "Q5") (pin "6") (pinfunction "FAULT_6") (pintype "bidirectional"))
    )
    (net (code "101") (name "unconnected-(U$1-AREF-Pad18)") (class "Default")
      (node (ref "U$1") (pin "18") (pinfunction "AREF_18") (pintype "bidirectional"))
    )
    (net (code "102") (name "unconnected-(U$1-RST-Pad7)") (class "Default")
      (node (ref "U$1") (pin "7") (pinfunction "RST_7") (pintype "bidirectional"))
    )
    (net (code "103") (name "unconnected-(U$1-VBUS-Pad16)") (class "Default")
      (node (ref "U$1") (pin "16") (pinfunction "VBUS_16") (pintype "bidirectional"))
    )
    (net (code "104") (name "unconnected-(U$4-Pad4)") (class "Default")
      (node (ref "U$4") (pin "4") (pinfunction "4_4") (pintype "bidirectional"))
    )
    (net (code "105") (name "unconnected-(U$4-Pad5)") (class "Default")
      (node (ref "U$4") (pin "5") (pinfunction "5_5") (pintype "bidirectional"))
    )
    (net (code "106") (name "unconnected-(U$6-FAULT-Pad3)") (class "Default")
      (node (ref "U$6") (pin "3") (pinfunction "FAULT_3") (pintype "bidirectional"))
    )
    (net (code "107") (name "unconnected-(U$6-TIMER-Pad2)") (class "Default")
      (node (ref "U$6") (pin "2") (pinfunction "TIMER_2") (pintype "bidirectional"))
    )
    (net (code "108") (name "unconnected-(U$7-FAULT-Pad3)") (class "Default")
      (node (ref "U$7") (pin "3") (pinfunction "FAULT_3") (pintype "bidirectional"))
    )
    (net (code "109") (name "unconnected-(U$7-TIMER-Pad2)") (class "Default")
      (node (ref "U$7") (pin "2") (pinfunction "TIMER_2") (pintype "bidirectional"))
    )
    (net (code "110") (name "unconnected-(U$8-FAULT-Pad3)") (class "Default")
      (node (ref "U$8") (pin "3") (pinfunction "FAULT_3") (pintype "bidirectional"))
    )
    (net (code "111") (name "unconnected-(U$8-TIMER-Pad2)") (class "Default")
      (node (ref "U$8") (pin "2") (pinfunction "TIMER_2") (pintype "bidirectional"))
    )
    (net (code "112") (name "unconnected-(U$9-FAULT-Pad3)") (class "Default")
      (node (ref "U$9") (pin "3") (pinfunction "FAULT_3") (pintype "bidirectional"))
    )
    (net (code "113") (name "unconnected-(U$9-TIMER-Pad2)") (class "Default")
      (node (ref "U$9") (pin "2") (pinfunction "TIMER_2") (pintype "bidirectional"))
    )
    (net (code "114") (name "unconnected-(U$10-FAULT-Pad3)") (class "Default")
      (node (ref "U$10") (pin "3") (pinfunction "FAULT_3") (pintype "bidirectional"))
    )
    (net (code "115") (name "unconnected-(U$10-TIMER-Pad2)") (class "Default")
      (node (ref "U$10") (pin "2") (pinfunction "TIMER_2") (pintype "bidirectional"))
    )
    (net (code "116") (name "unconnected-(U$11-FAULT-Pad3)") (class "Default")
      (node (ref "U$11") (pin "3") (pinfunction "FAULT_3") (pintype "bidirectional"))
    )
    (net (code "117") (name "unconnected-(U$11-TIMER-Pad2)") (class "Default")
      (node (ref "U$11") (pin "2") (pinfunction "TIMER_2") (pintype "bidirectional"))
    )
    (net (code "118") (name "unconnected-(U$12-FAULT-Pad3)") (class "Default")
      (node (ref "U$12") (pin "3") (pinfunction "FAULT_3") (pintype "bidirectional"))
    )
    (net (code "119") (name "unconnected-(U$12-TIMER-Pad2)") (class "Default")
      (node (ref "U$12") (pin "2") (pinfunction "TIMER_2") (pintype "bidirectional"))
    )
    (net (code "120") (name "unconnected-(U$13-FAULT-Pad3)") (class "Default")
      (node (ref "U$13") (pin "3") (pinfunction "FAULT_3") (pintype "bidirectional"))
    )
    (net (code "121") (name "unconnected-(U$13-TIMER-Pad2)") (class "Default")
      (node (ref "U$13") (pin "2") (pinfunction "TIMER_2") (pintype "bidirectional"))
    )
    (net (code "122") (name "unconnected-(VADER-5V-EXT-INHIBIT-Pad3)") (class "Default")
      (node (ref "VADER-5V-EXT") (pin "3") (pinfunction "INHIBIT_3") (pintype "bidirectional"))
    )
  )
)
